# io-board-c-2.net
KiCad netlist of a schematic drawn in EAGLE
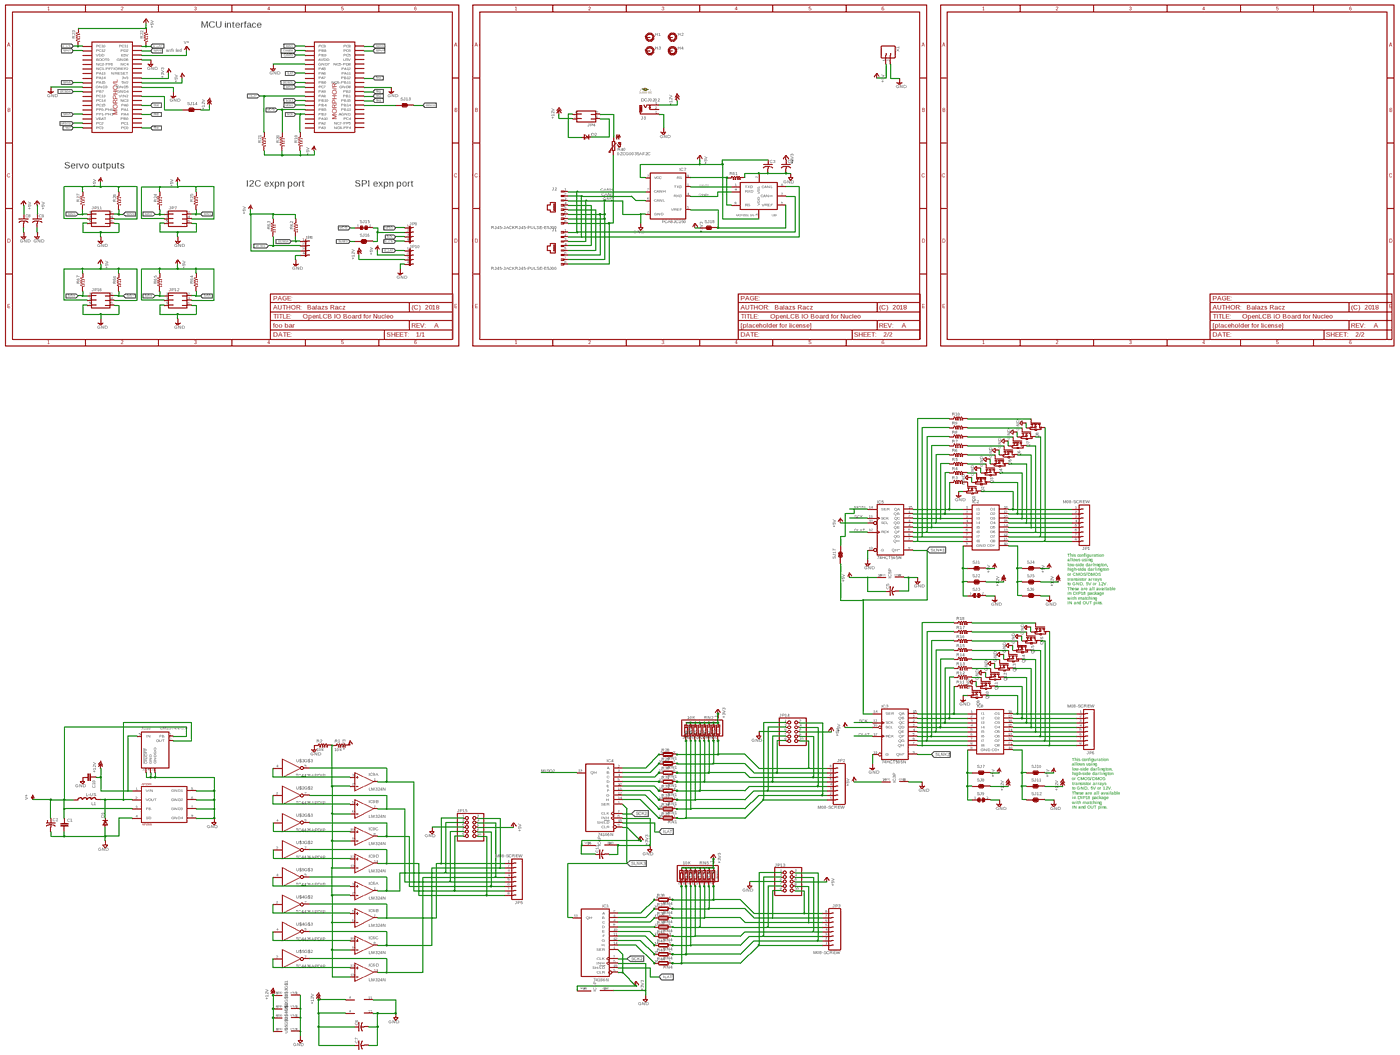
[diagram p0: schematic, sheet 1, overview]
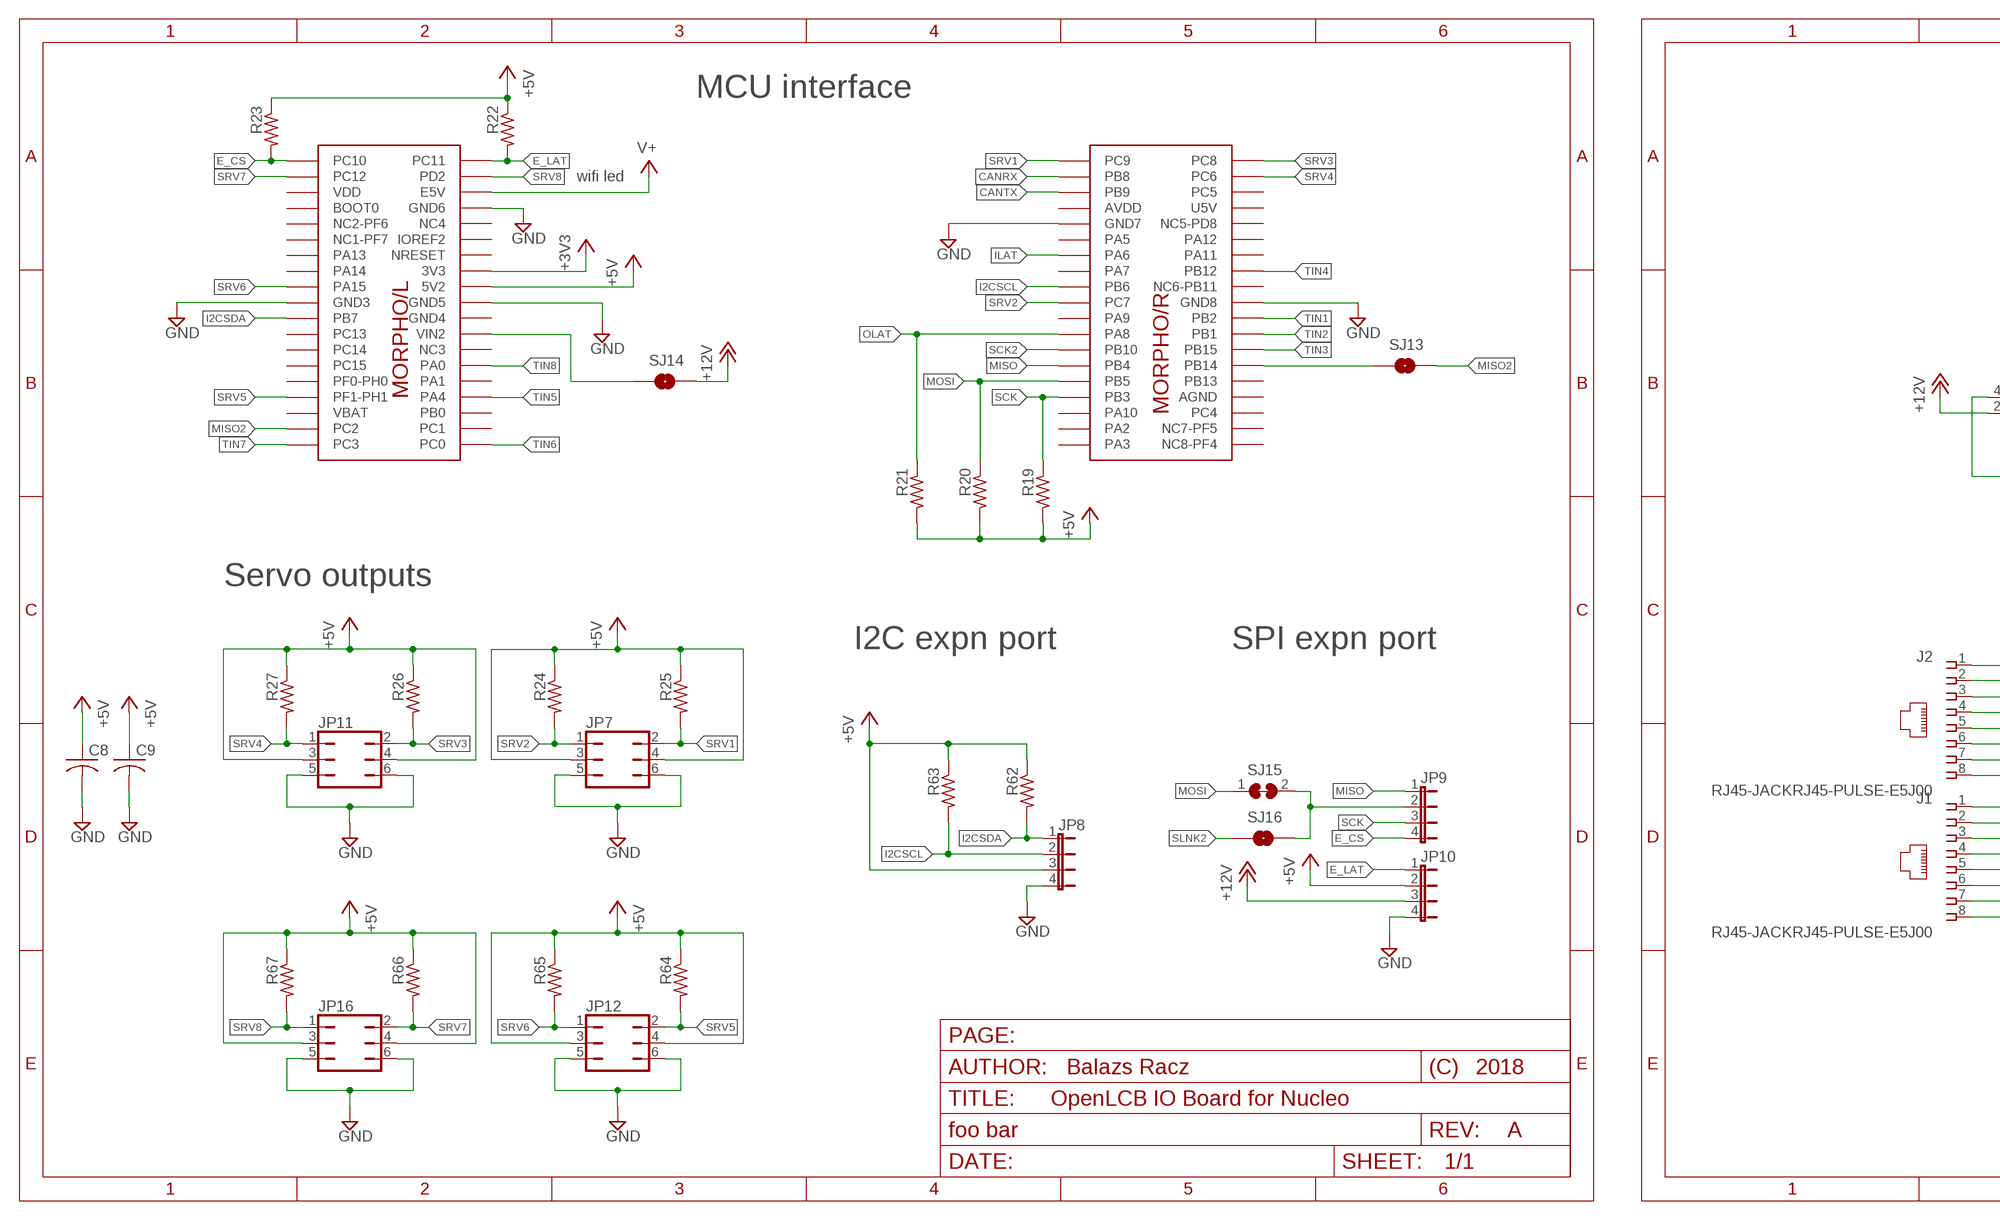
[diagram p1: schematic, sheet 1, part 1 of 4]
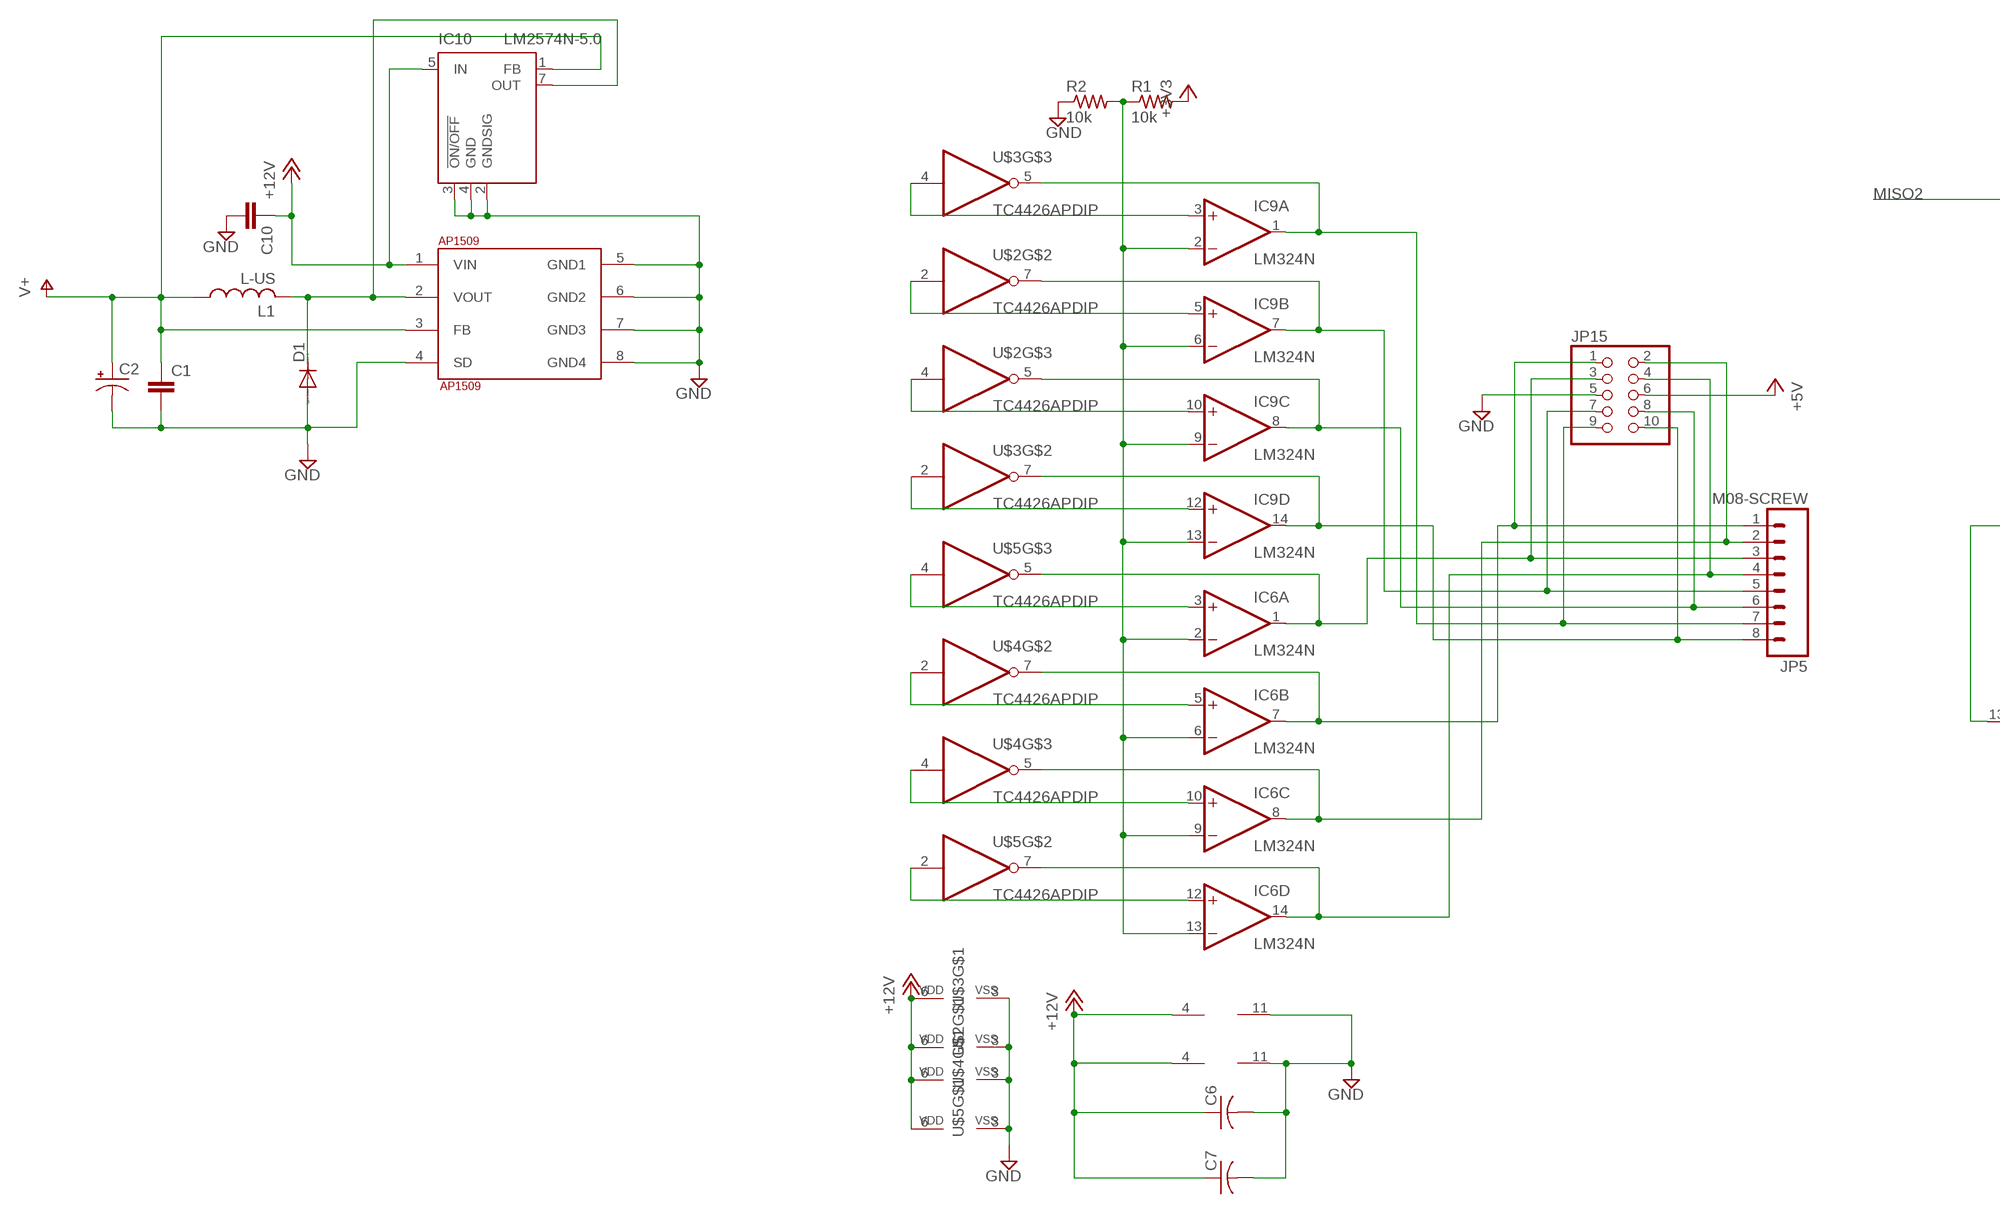
[diagram p2: schematic, sheet 1, part 2 of 4]
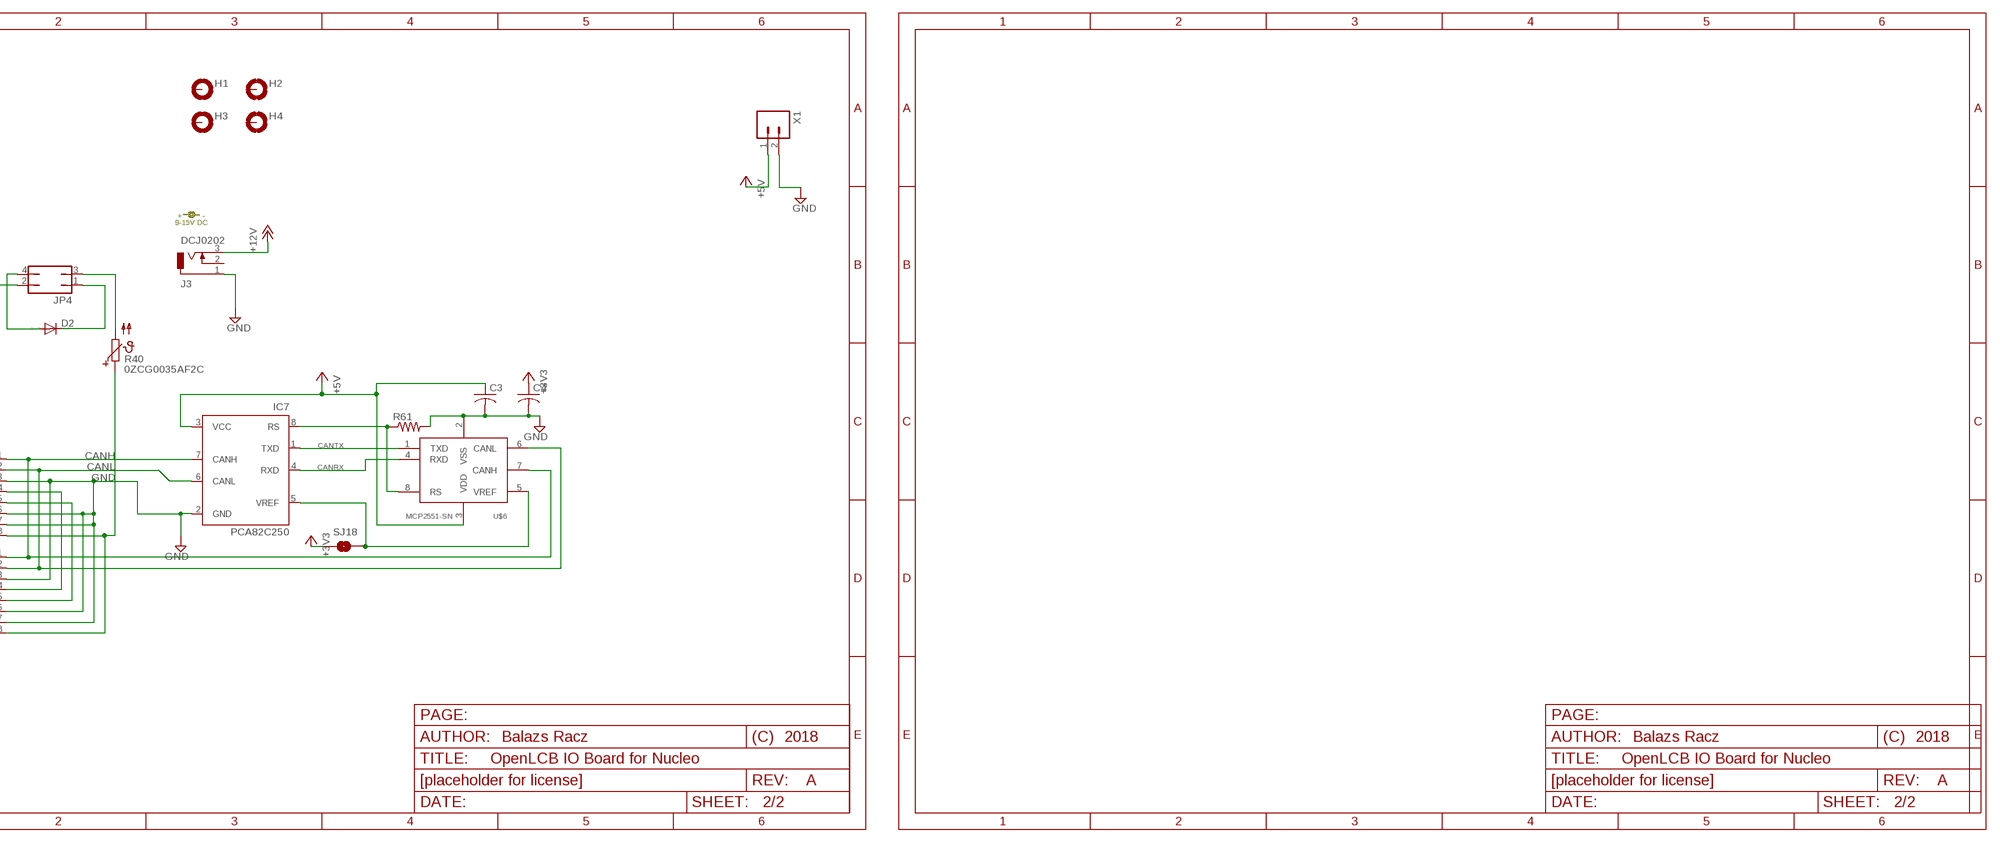
[diagram p3: schematic, sheet 1, part 3 of 4]
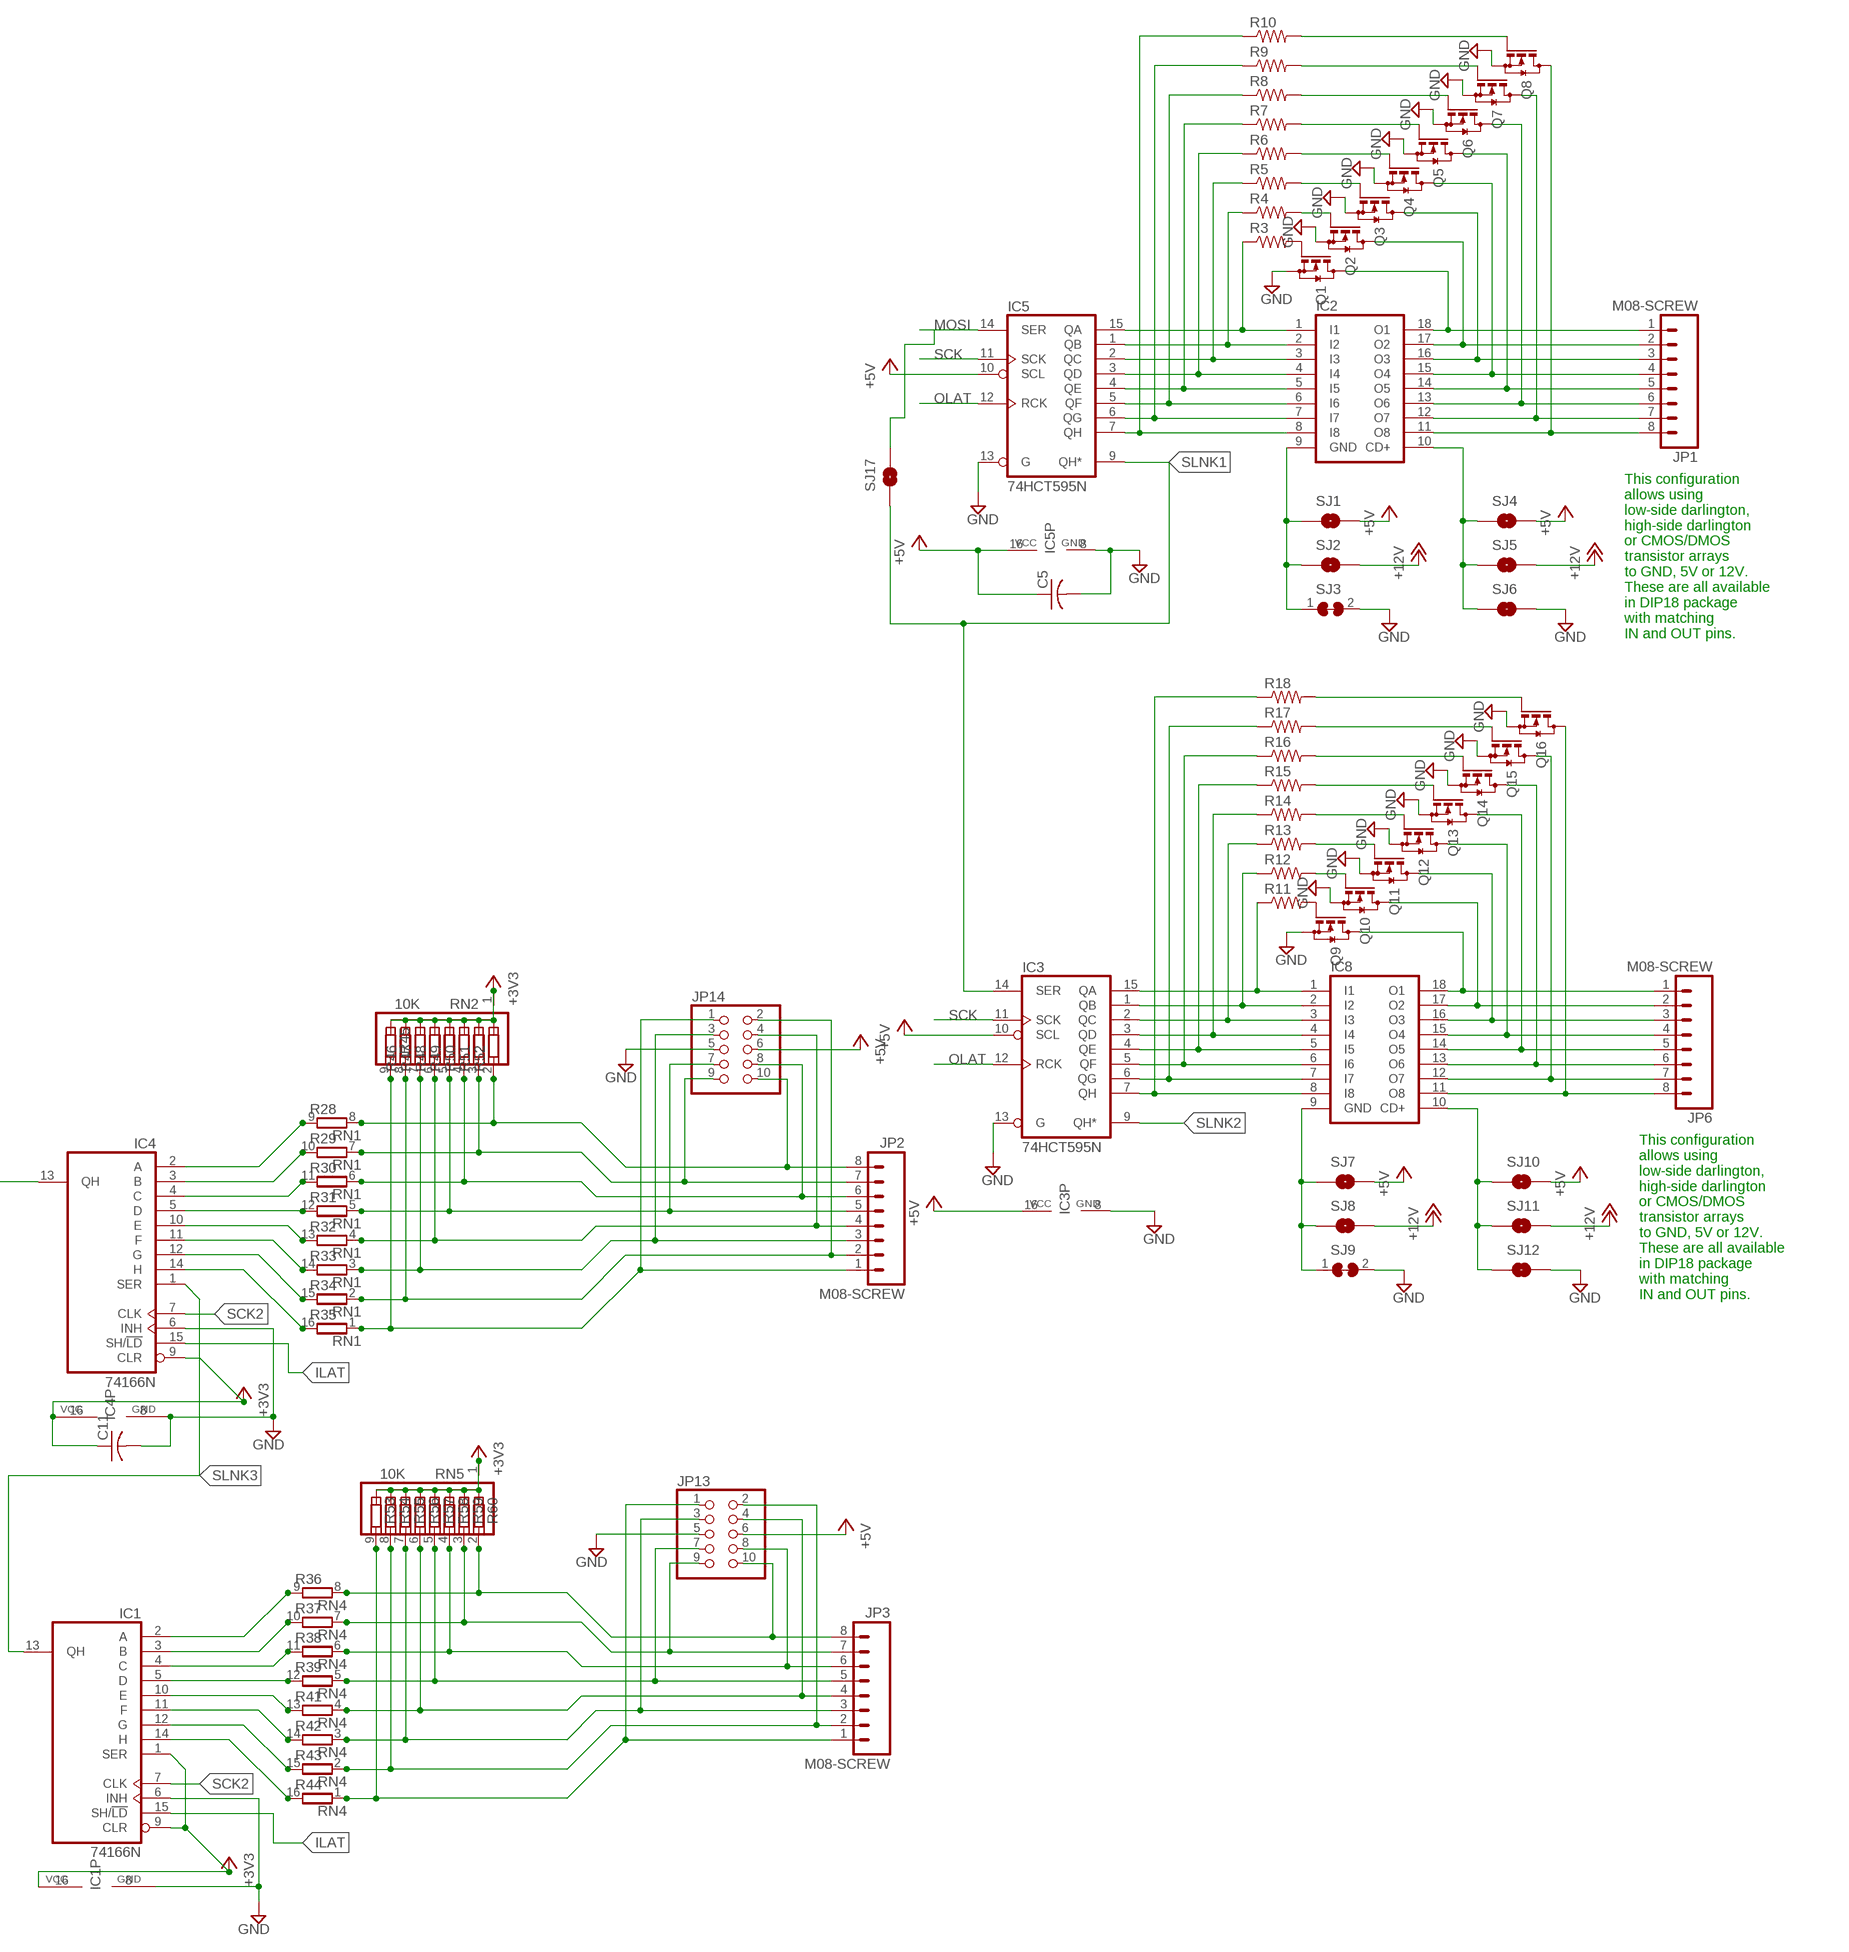
[diagram p4: schematic, sheet 1, part 4 of 4]

(export (version "E")
  (design (tool "Eeschema 10.0.6"))
  (components
    (comp (ref "+12V")
      (value "9-15V DC")
      (footprint "eagle-import:POWER_USAGE")
      (libsource (lib "eagle-import") (part "DOC-POWER_LABEL"))
    )
    (comp (ref "AP1509")
      (value "AP1509")
      (footprint "eagle-import:SO-08")
      (libsource (lib "eagle-import") (part "AP1509"))
    )
    (comp (ref "C1")
      (value "C-EUC1206")
      (footprint "eagle-import:C1206")
      (libsource (lib "eagle-import") (part "C-EUC1206"))
    )
    (comp (ref "C2")
      (value "CPOL-USE2.5-5")
      (footprint "eagle-import:E2,5-5")
      (libsource (lib "eagle-import") (part "CPOL-USE2.5-5"))
    )
    (comp (ref "C3")
      (value "C-USC0805")
      (footprint "eagle-import:C0805")
      (libsource (lib "eagle-import") (part "C-USC0805"))
    )
    (comp (ref "C4")
      (value "C-USC0805")
      (footprint "eagle-import:C0805")
      (libsource (lib "eagle-import") (part "C-USC0805"))
    )
    (comp (ref "C5")
      (value "C-USC0805")
      (footprint "eagle-import:C0805")
      (libsource (lib "eagle-import") (part "C-USC0805"))
    )
    (comp (ref "C6")
      (value "C-USC1206")
      (footprint "eagle-import:C1206")
      (libsource (lib "eagle-import") (part "C-USC1206"))
    )
    (comp (ref "C7")
      (value "C-USC1206")
      (footprint "eagle-import:C1206")
      (libsource (lib "eagle-import") (part "C-USC1206"))
    )
    (comp (ref "C8")
      (value "C-USC1206")
      (footprint "eagle-import:C1206")
      (libsource (lib "eagle-import") (part "C-USC1206"))
    )
    (comp (ref "C9")
      (value "C-USC1206")
      (footprint "eagle-import:C1206")
      (libsource (lib "eagle-import") (part "C-USC1206"))
    )
    (comp (ref "C10")
      (value "C-EUC1206")
      (footprint "eagle-import:C1206")
      (libsource (lib "eagle-import") (part "C-EUC1206"))
    )
    (comp (ref "C11")
      (value "C-USC0805")
      (footprint "eagle-import:C0805")
      (libsource (lib "eagle-import") (part "C-USC0805"))
    )
    (comp (ref "D1")
      (value "DIODE-DO41-7.6")
      (footprint "eagle-import:DO41-7.6")
      (libsource (lib "eagle-import") (part "DIODE-DO41-7.6"))
    )
    (comp (ref "D2")
      (value "DIODE-DO41-7.6")
      (footprint "eagle-import:DO41-7.6")
      (libsource (lib "eagle-import") (part "DIODE-DO41-7.6"))
    )
    (comp (ref "H1")
      (value "MOUNT-PAD-ROUND3.3")
      (footprint "eagle-import:3,3-PAD")
      (libsource (lib "eagle-import") (part "MOUNT-PAD-ROUND3.3"))
    )
    (comp (ref "H2")
      (value "MOUNT-PAD-ROUND3.3")
      (footprint "eagle-import:3,3-PAD")
      (libsource (lib "eagle-import") (part "MOUNT-PAD-ROUND3.3"))
    )
    (comp (ref "H3")
      (value "MOUNT-PAD-ROUND3.3")
      (footprint "eagle-import:3,3-PAD")
      (libsource (lib "eagle-import") (part "MOUNT-PAD-ROUND3.3"))
    )
    (comp (ref "H4")
      (value "MOUNT-PAD-ROUND3.3")
      (footprint "eagle-import:3,3-PAD")
      (libsource (lib "eagle-import") (part "MOUNT-PAD-ROUND3.3"))
    )
    (comp (ref "IC1")
      (value "74166N")
      (footprint "eagle-import:DIL16")
      (libsource (lib "eagle-import") (part "74166N"))
    )
    (comp (ref "IC2")
      (value "ULN2803A")
      (footprint "eagle-import:DIL18-THIN")
      (libsource (lib "eagle-import") (part "ULN2803A"))
    )
    (comp (ref "IC3")
      (value "74HCT595N")
      (footprint "eagle-import:DIL16")
      (libsource (lib "eagle-import") (part "74595NHCT"))
    )
    (comp (ref "IC4")
      (value "74166N")
      (footprint "eagle-import:DIL16")
      (libsource (lib "eagle-import") (part "74166N"))
    )
    (comp (ref "IC5")
      (value "74HCT595N")
      (footprint "eagle-import:DIL16")
      (libsource (lib "eagle-import") (part "74595NHCT"))
    )
    (comp (ref "IC6")
      (value "LM324N")
      (footprint "eagle-import:DIL14")
      (libsource (lib "eagle-import") (part "LM324N"))
    )
    (comp (ref "IC7")
      (value "PCA82C250")
      (footprint "eagle-import:DIL08")
      (libsource (lib "eagle-import") (part "PCA82C250"))
    )
    (comp (ref "IC8")
      (value "ULN2803A")
      (footprint "eagle-import:DIL18-THIN")
      (libsource (lib "eagle-import") (part "ULN2803A"))
    )
    (comp (ref "IC9")
      (value "LM324N")
      (footprint "eagle-import:DIL14")
      (libsource (lib "eagle-import") (part "LM324N"))
    )
    (comp (ref "IC10")
      (value "LM2574N-5.0")
      (footprint "eagle-import:DIL08")
      (libsource (lib "eagle-import") (part "LM2574?-N5.0"))
    )
    (comp (ref "J1")
      (value "RJ45-JACKRJ45-PULSE-E5J00")
      (footprint "eagle-import:RJ45-PULSE-E5J88")
      (libsource (lib "eagle-import") (part "RJ45-JACKRJ45-PULSE-E5J00"))
    )
    (comp (ref "J2")
      (value "RJ45-JACKRJ45-PULSE-E5J00")
      (footprint "eagle-import:RJ45-PULSE-E5J88")
      (libsource (lib "eagle-import") (part "RJ45-JACKRJ45-PULSE-E5J00"))
    )
    (comp (ref "J3")
      (value "DCJ0202")
      (footprint "eagle-import:DCJ0202")
      (libsource (lib "eagle-import") (part "DCJ0202"))
    )
    (comp (ref "JP1")
      (value "M08-SCREW")
      (footprint "eagle-import:1X08_TERMINAL")
      (libsource (lib "eagle-import") (part "M08-SCREW"))
    )
    (comp (ref "JP2")
      (value "M08-SCREW")
      (footprint "eagle-import:1X08_TERMINAL")
      (libsource (lib "eagle-import") (part "M08-SCREW"))
    )
    (comp (ref "JP3")
      (value "M08-SCREW")
      (footprint "eagle-import:1X08_TERMINAL")
      (libsource (lib "eagle-import") (part "M08-SCREW"))
    )
    (comp (ref "JP4")
      (value "JP2Q")
      (footprint "eagle-import:JP2Q")
      (libsource (lib "eagle-import") (part "JP2Q"))
    )
    (comp (ref "JP5")
      (value "M08-SCREW")
      (footprint "eagle-import:1X08_TERMINAL")
      (libsource (lib "eagle-import") (part "M08-SCREW"))
    )
    (comp (ref "JP6")
      (value "M08-SCREW")
      (footprint "eagle-import:1X08_TERMINAL")
      (libsource (lib "eagle-import") (part "M08-SCREW"))
    )
    (comp (ref "JP7")
      (value "JP3Q")
      (footprint "eagle-import:JP3Q")
      (libsource (lib "eagle-import") (part "JP3Q"))
    )
    (comp (ref "JP8")
      (value "JP4-FLAT")
      (footprint "eagle-import:JP4F")
      (libsource (lib "eagle-import") (part "JP4-FLAT"))
    )
    (comp (ref "JP9")
      (value "JP4-FLAT")
      (footprint "eagle-import:JP4F")
      (libsource (lib "eagle-import") (part "JP4-FLAT"))
    )
    (comp (ref "JP10")
      (value "JP4-FLAT")
      (footprint "eagle-import:JP4F")
      (libsource (lib "eagle-import") (part "JP4-FLAT"))
    )
    (comp (ref "JP11")
      (value "JP3Q")
      (footprint "eagle-import:JP3Q")
      (libsource (lib "eagle-import") (part "JP3Q"))
    )
    (comp (ref "JP12")
      (value "JP3Q")
      (footprint "eagle-import:JP3Q")
      (libsource (lib "eagle-import") (part "JP3Q"))
    )
    (comp (ref "JP13")
      (value "PINHD-2X5CN")
      (footprint "eagle-import:CON10M")
      (libsource (lib "eagle-import") (part "PINHD-2X5CN"))
    )
    (comp (ref "JP14")
      (value "PINHD-2X5CN")
      (footprint "eagle-import:CON10M")
      (libsource (lib "eagle-import") (part "PINHD-2X5CN"))
    )
    (comp (ref "JP15")
      (value "PINHD-2X5CN")
      (footprint "eagle-import:CON10M")
      (libsource (lib "eagle-import") (part "PINHD-2X5CN"))
    )
    (comp (ref "JP16")
      (value "JP3Q")
      (footprint "eagle-import:JP3Q")
      (libsource (lib "eagle-import") (part "JP3Q"))
    )
    (comp (ref "L1")
      (value "L-US")
      (footprint "eagle-import:L5-8,5")
      (libsource (lib "eagle-import") (part "L-US"))
    )
    (comp (ref "Q1")
      (value "BSS123")
      (footprint "eagle-import:SOT23")
      (libsource (lib "eagle-import") (part "BSS123"))
    )
    (comp (ref "Q2")
      (value "BSS123")
      (footprint "eagle-import:SOT23")
      (libsource (lib "eagle-import") (part "BSS123"))
    )
    (comp (ref "Q3")
      (value "BSS123")
      (footprint "eagle-import:SOT23")
      (libsource (lib "eagle-import") (part "BSS123"))
    )
    (comp (ref "Q4")
      (value "BSS123")
      (footprint "eagle-import:SOT23")
      (libsource (lib "eagle-import") (part "BSS123"))
    )
    (comp (ref "Q5")
      (value "BSS123")
      (footprint "eagle-import:SOT23")
      (libsource (lib "eagle-import") (part "BSS123"))
    )
    (comp (ref "Q6")
      (value "BSS123")
      (footprint "eagle-import:SOT23")
      (libsource (lib "eagle-import") (part "BSS123"))
    )
    (comp (ref "Q7")
      (value "BSS123")
      (footprint "eagle-import:SOT23")
      (libsource (lib "eagle-import") (part "BSS123"))
    )
    (comp (ref "Q8")
      (value "BSS123")
      (footprint "eagle-import:SOT23")
      (libsource (lib "eagle-import") (part "BSS123"))
    )
    (comp (ref "Q9")
      (value "BSS123")
      (footprint "eagle-import:SOT23")
      (libsource (lib "eagle-import") (part "BSS123"))
    )
    (comp (ref "Q10")
      (value "BSS123")
      (footprint "eagle-import:SOT23")
      (libsource (lib "eagle-import") (part "BSS123"))
    )
    (comp (ref "Q11")
      (value "BSS123")
      (footprint "eagle-import:SOT23")
      (libsource (lib "eagle-import") (part "BSS123"))
    )
    (comp (ref "Q12")
      (value "BSS123")
      (footprint "eagle-import:SOT23")
      (libsource (lib "eagle-import") (part "BSS123"))
    )
    (comp (ref "Q13")
      (value "BSS123")
      (footprint "eagle-import:SOT23")
      (libsource (lib "eagle-import") (part "BSS123"))
    )
    (comp (ref "Q14")
      (value "BSS123")
      (footprint "eagle-import:SOT23")
      (libsource (lib "eagle-import") (part "BSS123"))
    )
    (comp (ref "Q15")
      (value "BSS123")
      (footprint "eagle-import:SOT23")
      (libsource (lib "eagle-import") (part "BSS123"))
    )
    (comp (ref "Q16")
      (value "BSS123")
      (footprint "eagle-import:SOT23")
      (libsource (lib "eagle-import") (part "BSS123"))
    )
    (comp (ref "R1")
      (value "10k")
      (footprint "eagle-import:R0805")
      (libsource (lib "eagle-import") (part "R-US_R0805"))
    )
    (comp (ref "R2")
      (value "10k")
      (footprint "eagle-import:R0805")
      (libsource (lib "eagle-import") (part "R-US_R0805"))
    )
    (comp (ref "R3")
      (value "R-US_R0603")
      (footprint "eagle-import:R0603")
      (libsource (lib "eagle-import") (part "R-US_R0603"))
    )
    (comp (ref "R4")
      (value "R-US_R0603")
      (footprint "eagle-import:R0603")
      (libsource (lib "eagle-import") (part "R-US_R0603"))
    )
    (comp (ref "R5")
      (value "R-US_R0603")
      (footprint "eagle-import:R0603")
      (libsource (lib "eagle-import") (part "R-US_R0603"))
    )
    (comp (ref "R6")
      (value "R-US_R0603")
      (footprint "eagle-import:R0603")
      (libsource (lib "eagle-import") (part "R-US_R0603"))
    )
    (comp (ref "R7")
      (value "R-US_R0603")
      (footprint "eagle-import:R0603")
      (libsource (lib "eagle-import") (part "R-US_R0603"))
    )
    (comp (ref "R8")
      (value "R-US_R0603")
      (footprint "eagle-import:R0603")
      (libsource (lib "eagle-import") (part "R-US_R0603"))
    )
    (comp (ref "R9")
      (value "R-US_R0603")
      (footprint "eagle-import:R0603")
      (libsource (lib "eagle-import") (part "R-US_R0603"))
    )
    (comp (ref "R10")
      (value "R-US_R0603")
      (footprint "eagle-import:R0603")
      (libsource (lib "eagle-import") (part "R-US_R0603"))
    )
    (comp (ref "R11")
      (value "R-US_R0603")
      (footprint "eagle-import:R0603")
      (libsource (lib "eagle-import") (part "R-US_R0603"))
    )
    (comp (ref "R12")
      (value "R-US_R0603")
      (footprint "eagle-import:R0603")
      (libsource (lib "eagle-import") (part "R-US_R0603"))
    )
    (comp (ref "R13")
      (value "R-US_R0603")
      (footprint "eagle-import:R0603")
      (libsource (lib "eagle-import") (part "R-US_R0603"))
    )
    (comp (ref "R14")
      (value "R-US_R0603")
      (footprint "eagle-import:R0603")
      (libsource (lib "eagle-import") (part "R-US_R0603"))
    )
    (comp (ref "R15")
      (value "R-US_R0603")
      (footprint "eagle-import:R0603")
      (libsource (lib "eagle-import") (part "R-US_R0603"))
    )
    (comp (ref "R16")
      (value "R-US_R0603")
      (footprint "eagle-import:R0603")
      (libsource (lib "eagle-import") (part "R-US_R0603"))
    )
    (comp (ref "R17")
      (value "R-US_R0603")
      (footprint "eagle-import:R0603")
      (libsource (lib "eagle-import") (part "R-US_R0603"))
    )
    (comp (ref "R18")
      (value "R-US_R0603")
      (footprint "eagle-import:R0603")
      (libsource (lib "eagle-import") (part "R-US_R0603"))
    )
    (comp (ref "R19")
      (value "R-US_R0805")
      (footprint "eagle-import:R0805")
      (libsource (lib "eagle-import") (part "rcl_334_R-US_R0805"))
    )
    (comp (ref "R20")
      (value "R-US_R0805")
      (footprint "eagle-import:R0805")
      (libsource (lib "eagle-import") (part "rcl_334_R-US_R0805"))
    )
    (comp (ref "R21")
      (value "R-US_R0805")
      (footprint "eagle-import:R0805")
      (libsource (lib "eagle-import") (part "rcl_334_R-US_R0805"))
    )
    (comp (ref "R22")
      (value "R-US_R0805")
      (footprint "eagle-import:R0805")
      (libsource (lib "eagle-import") (part "rcl_334_R-US_R0805"))
    )
    (comp (ref "R23")
      (value "R-US_R0805")
      (footprint "eagle-import:R0805")
      (libsource (lib "eagle-import") (part "rcl_334_R-US_R0805"))
    )
    (comp (ref "R24")
      (value "R-US_R0805")
      (footprint "eagle-import:R0805")
      (libsource (lib "eagle-import") (part "rcl_334_R-US_R0805"))
    )
    (comp (ref "R25")
      (value "R-US_R0805")
      (footprint "eagle-import:R0805")
      (libsource (lib "eagle-import") (part "rcl_334_R-US_R0805"))
    )
    (comp (ref "R26")
      (value "R-US_R0805")
      (footprint "eagle-import:R0805")
      (libsource (lib "eagle-import") (part "rcl_334_R-US_R0805"))
    )
    (comp (ref "R27")
      (value "R-US_R0805")
      (footprint "eagle-import:R0805")
      (libsource (lib "eagle-import") (part "rcl_334_R-US_R0805"))
    )
    (comp (ref "R28")
      (value "R-EU_R0603")
      (footprint "eagle-import:R0603")
      (libsource (lib "eagle-import") (part "R-EU_R0603"))
    )
    (comp (ref "R29")
      (value "R-EU_R0603")
      (footprint "eagle-import:R0603")
      (libsource (lib "eagle-import") (part "R-EU_R0603"))
    )
    (comp (ref "R30")
      (value "R-EU_R0603")
      (footprint "eagle-import:R0603")
      (libsource (lib "eagle-import") (part "R-EU_R0603"))
    )
    (comp (ref "R31")
      (value "R-EU_R0603")
      (footprint "eagle-import:R0603")
      (libsource (lib "eagle-import") (part "R-EU_R0603"))
    )
    (comp (ref "R32")
      (value "R-EU_R0603")
      (footprint "eagle-import:R0603")
      (libsource (lib "eagle-import") (part "R-EU_R0603"))
    )
    (comp (ref "R33")
      (value "R-EU_R0603")
      (footprint "eagle-import:R0603")
      (libsource (lib "eagle-import") (part "R-EU_R0603"))
    )
    (comp (ref "R34")
      (value "R-EU_R0603")
      (footprint "eagle-import:R0603")
      (libsource (lib "eagle-import") (part "R-EU_R0603"))
    )
    (comp (ref "R35")
      (value "R-EU_R0603")
      (footprint "eagle-import:R0603")
      (libsource (lib "eagle-import") (part "R-EU_R0603"))
    )
    (comp (ref "R36")
      (value "R-EU_R0603")
      (footprint "eagle-import:R0603")
      (libsource (lib "eagle-import") (part "R-EU_R0603"))
    )
    (comp (ref "R37")
      (value "R-EU_R0603")
      (footprint "eagle-import:R0603")
      (libsource (lib "eagle-import") (part "R-EU_R0603"))
    )
    (comp (ref "R38")
      (value "R-EU_R0603")
      (footprint "eagle-import:R0603")
      (libsource (lib "eagle-import") (part "R-EU_R0603"))
    )
    (comp (ref "R39")
      (value "R-EU_R0603")
      (footprint "eagle-import:R0603")
      (libsource (lib "eagle-import") (part "R-EU_R0603"))
    )
    (comp (ref "R40")
      (value "0ZCG0035AF2C")
      (footprint "eagle-import:PTC1812")
      (libsource (lib "eagle-import") (part "PTC_1812"))
    )
    (comp (ref "R41")
      (value "R-EU_R0603")
      (footprint "eagle-import:R0603")
      (libsource (lib "eagle-import") (part "R-EU_R0603"))
    )
    (comp (ref "R42")
      (value "R-EU_R0603")
      (footprint "eagle-import:R0603")
      (libsource (lib "eagle-import") (part "R-EU_R0603"))
    )
    (comp (ref "R43")
      (value "R-EU_R0603")
      (footprint "eagle-import:R0603")
      (libsource (lib "eagle-import") (part "R-EU_R0603"))
    )
    (comp (ref "R44")
      (value "R-EU_R0603")
      (footprint "eagle-import:R0603")
      (libsource (lib "eagle-import") (part "R-EU_R0603"))
    )
    (comp (ref "R45")
      (value "R-EU_R0603")
      (footprint "eagle-import:R0603")
      (libsource (lib "eagle-import") (part "R-EU_R0603"))
    )
    (comp (ref "R46")
      (value "R-EU_R0603")
      (footprint "eagle-import:R0603")
      (libsource (lib "eagle-import") (part "R-EU_R0603"))
    )
    (comp (ref "R47")
      (value "R-EU_R0603")
      (footprint "eagle-import:R0603")
      (libsource (lib "eagle-import") (part "R-EU_R0603"))
    )
    (comp (ref "R48")
      (value "R-EU_R0603")
      (footprint "eagle-import:R0603")
      (libsource (lib "eagle-import") (part "R-EU_R0603"))
    )
    (comp (ref "R49")
      (value "R-EU_R0603")
      (footprint "eagle-import:R0603")
      (libsource (lib "eagle-import") (part "R-EU_R0603"))
    )
    (comp (ref "R50")
      (value "R-EU_R0603")
      (footprint "eagle-import:R0603")
      (libsource (lib "eagle-import") (part "R-EU_R0603"))
    )
    (comp (ref "R51")
      (value "R-EU_R0603")
      (footprint "eagle-import:R0603")
      (libsource (lib "eagle-import") (part "R-EU_R0603"))
    )
    (comp (ref "R52")
      (value "R-EU_R0603")
      (footprint "eagle-import:R0603")
      (libsource (lib "eagle-import") (part "R-EU_R0603"))
    )
    (comp (ref "R53")
      (value "R-EU_R0603")
      (footprint "eagle-import:R0603")
      (libsource (lib "eagle-import") (part "R-EU_R0603"))
    )
    (comp (ref "R54")
      (value "R-EU_R0603")
      (footprint "eagle-import:R0603")
      (libsource (lib "eagle-import") (part "R-EU_R0603"))
    )
    (comp (ref "R55")
      (value "R-EU_R0603")
      (footprint "eagle-import:R0603")
      (libsource (lib "eagle-import") (part "R-EU_R0603"))
    )
    (comp (ref "R56")
      (value "R-EU_R0603")
      (footprint "eagle-import:R0603")
      (libsource (lib "eagle-import") (part "R-EU_R0603"))
    )
    (comp (ref "R57")
      (value "R-EU_R0603")
      (footprint "eagle-import:R0603")
      (libsource (lib "eagle-import") (part "R-EU_R0603"))
    )
    (comp (ref "R58")
      (value "R-EU_R0603")
      (footprint "eagle-import:R0603")
      (libsource (lib "eagle-import") (part "R-EU_R0603"))
    )
    (comp (ref "R59")
      (value "R-EU_R0603")
      (footprint "eagle-import:R0603")
      (libsource (lib "eagle-import") (part "R-EU_R0603"))
    )
    (comp (ref "R60")
      (value "R-EU_R0603")
      (footprint "eagle-import:R0603")
      (libsource (lib "eagle-import") (part "R-EU_R0603"))
    )
    (comp (ref "R61")
      (value "R-US_R0805")
      (footprint "eagle-import:R0805")
      (libsource (lib "eagle-import") (part "rcl_334_R-US_R0805"))
    )
    (comp (ref "R62")
      (value "R-US_R0805")
      (footprint "eagle-import:R0805")
      (libsource (lib "eagle-import") (part "rcl_334_R-US_R0805"))
    )
    (comp (ref "R63")
      (value "R-US_R0805")
      (footprint "eagle-import:R0805")
      (libsource (lib "eagle-import") (part "rcl_334_R-US_R0805"))
    )
    (comp (ref "R64")
      (value "R-US_R0805")
      (footprint "eagle-import:R0805")
      (libsource (lib "eagle-import") (part "rcl_334_R-US_R0805"))
    )
    (comp (ref "R65")
      (value "R-US_R0805")
      (footprint "eagle-import:R0805")
      (libsource (lib "eagle-import") (part "rcl_334_R-US_R0805"))
    )
    (comp (ref "R66")
      (value "R-US_R0805")
      (footprint "eagle-import:R0805")
      (libsource (lib "eagle-import") (part "rcl_334_R-US_R0805"))
    )
    (comp (ref "R67")
      (value "R-US_R0805")
      (footprint "eagle-import:R0805")
      (libsource (lib "eagle-import") (part "rcl_334_R-US_R0805"))
    )
    (comp (ref "RN1")
      (value "8R-P")
      (footprint "eagle-import:DIL16")
      (libsource (lib "eagle-import") (part "8R-P"))
    )
    (comp (ref "RN2")
      (value "10K")
      (footprint "eagle-import:SIL9")
      (libsource (lib "eagle-import") (part "G08R"))
    )
    (comp (ref "RN4")
      (value "8R-P")
      (footprint "eagle-import:DIL16")
      (libsource (lib "eagle-import") (part "8R-P"))
    )
    (comp (ref "RN5")
      (value "10K")
      (footprint "eagle-import:SIL9")
      (libsource (lib "eagle-import") (part "G08R"))
    )
    (comp (ref "SJ1")
      (value "SJRND2")
      (footprint "eagle-import:SJ_RND2")
      (libsource (lib "eagle-import") (part "SJRND2"))
    )
    (comp (ref "SJ2")
      (value "SJRND2")
      (footprint "eagle-import:SJ_RND2")
      (libsource (lib "eagle-import") (part "SJRND2"))
    )
    (comp (ref "SJ3")
      (value "SJ-C")
      (footprint "eagle-import:SJW-C")
      (libsource (lib "eagle-import") (part "SJ-C"))
    )
    (comp (ref "SJ4")
      (value "SJRND2")
      (footprint "eagle-import:SJ_RND2")
      (libsource (lib "eagle-import") (part "SJRND2"))
    )
    (comp (ref "SJ5")
      (value "SJRND2")
      (footprint "eagle-import:SJ_RND2")
      (libsource (lib "eagle-import") (part "SJRND2"))
    )
    (comp (ref "SJ6")
      (value "SJRND2")
      (footprint "eagle-import:SJ_RND2")
      (libsource (lib "eagle-import") (part "SJRND2"))
    )
    (comp (ref "SJ7")
      (value "SJRND2")
      (footprint "eagle-import:SJ_RND2")
      (libsource (lib "eagle-import") (part "SJRND2"))
    )
    (comp (ref "SJ8")
      (value "SJRND2")
      (footprint "eagle-import:SJ_RND2")
      (libsource (lib "eagle-import") (part "SJRND2"))
    )
    (comp (ref "SJ9")
      (value "SJ-C")
      (footprint "eagle-import:SJW-C")
      (libsource (lib "eagle-import") (part "SJ-C"))
    )
    (comp (ref "SJ10")
      (value "SJRND2")
      (footprint "eagle-import:SJ_RND2")
      (libsource (lib "eagle-import") (part "SJRND2"))
    )
    (comp (ref "SJ11")
      (value "SJRND2")
      (footprint "eagle-import:SJ_RND2")
      (libsource (lib "eagle-import") (part "SJRND2"))
    )
    (comp (ref "SJ12")
      (value "SJRND2")
      (footprint "eagle-import:SJ_RND2")
      (libsource (lib "eagle-import") (part "SJRND2"))
    )
    (comp (ref "SJ13")
      (value "SJRND2")
      (footprint "eagle-import:SJ_RND2")
      (libsource (lib "eagle-import") (part "SJRND2"))
    )
    (comp (ref "SJ14")
      (value "SJRND2")
      (footprint "eagle-import:SJ_RND2")
      (libsource (lib "eagle-import") (part "SJRND2"))
    )
    (comp (ref "SJ15")
      (value "SJ-C")
      (footprint "eagle-import:SJW-C")
      (libsource (lib "eagle-import") (part "SJ-C"))
    )
    (comp (ref "SJ16")
      (value "SJRND2")
      (footprint "eagle-import:SJ_RND2")
      (libsource (lib "eagle-import") (part "SJRND2"))
    )
    (comp (ref "SJ17")
      (value "SJRND2")
      (footprint "eagle-import:SJ_RND2")
      (libsource (lib "eagle-import") (part "SJRND2"))
    )
    (comp (ref "SJ18")
      (value "SJRND2")
      (footprint "eagle-import:SJ_RND2")
      (libsource (lib "eagle-import") (part "SJRND2"))
    )
    (comp (ref "U$1")
      (value "NUCLEO_64_GENERIC")
      (footprint "eagle-import:NUCLEO_BRD_BASE64")
      (libsource (lib "eagle-import") (part "NUCLEO_64_GENERIC"))
    )
    (comp (ref "U$2")
      (value "TC4426APDIP")
      (footprint "eagle-import:DIL08-LONG")
      (libsource (lib "eagle-import") (part "TC4426APDIP"))
    )
    (comp (ref "U$3")
      (value "TC4426APDIP")
      (footprint "eagle-import:DIL08-LONG")
      (libsource (lib "eagle-import") (part "TC4426APDIP"))
    )
    (comp (ref "U$4")
      (value "TC4426APDIP")
      (footprint "eagle-import:DIL08-LONG")
      (libsource (lib "eagle-import") (part "TC4426APDIP"))
    )
    (comp (ref "U$5")
      (value "TC4426APDIP")
      (footprint "eagle-import:DIL08-LONG")
      (libsource (lib "eagle-import") (part "TC4426APDIP"))
    )
    (comp (ref "U$6")
      (value "MCP2551-SN")
      (footprint "eagle-import:SO-08")
      (libsource (lib "eagle-import") (part "MCP2551-SN"))
    )
    (comp (ref "X1")
      (value "CONNECTOR-M023.5MM-LOCK")
      (footprint "eagle-import:SCREWTERMINAL-3.5MM-2_LOCK")
      (libsource (lib "eagle-import") (part "CONNECTOR-M023.5MM-LOCK"))
    )
  )
  (nets
    (net (code "1") (name "+3V3") (class "Default")
      (node (ref "C11") (pin "1") (pinfunction "1_1") (pintype "passive"))
      (node (ref "C4") (pin "1") (pinfunction "1_1") (pintype "passive"))
      (node (ref "IC1") (pin "1") (pinfunction "SER_1") (pintype "input"))
      (node (ref "IC1") (pin "16") (pinfunction "VCC_16") (pintype "power_in"))
      (node (ref "IC1") (pin "9") (pinfunction "CLR_9") (pintype "input"))
      (node (ref "IC4") (pin "16") (pinfunction "VCC_16") (pintype "power_in"))
      (node (ref "IC4") (pin "9") (pinfunction "CLR_9") (pintype "input"))
      (node (ref "R1") (pin "2") (pinfunction "2_2") (pintype "passive"))
      (node (ref "R45") (pin "1") (pinfunction "1_1") (pintype "passive"))
      (node (ref "R46") (pin "2") (pinfunction "2_2") (pintype "passive"))
      (node (ref "R47") (pin "2") (pinfunction "2_2") (pintype "passive"))
      (node (ref "R48") (pin "2") (pinfunction "2_2") (pintype "passive"))
      (node (ref "R49") (pin "2") (pinfunction "2_2") (pintype "passive"))
      (node (ref "R50") (pin "2") (pinfunction "2_2") (pintype "passive"))
      (node (ref "R51") (pin "2") (pinfunction "2_2") (pintype "passive"))
      (node (ref "R52") (pin "2") (pinfunction "2_2") (pintype "passive"))
      (node (ref "R53") (pin "1") (pinfunction "1_1") (pintype "passive"))
      (node (ref "R54") (pin "1") (pinfunction "1_1") (pintype "passive"))
      (node (ref "R55") (pin "1") (pinfunction "1_1") (pintype "passive"))
      (node (ref "R56") (pin "1") (pinfunction "1_1") (pintype "passive"))
      (node (ref "R57") (pin "1") (pinfunction "1_1") (pintype "passive"))
      (node (ref "R58") (pin "1") (pinfunction "1_1") (pintype "passive"))
      (node (ref "R59") (pin "1") (pinfunction "1_1") (pintype "passive"))
      (node (ref "R60") (pin "1") (pinfunction "1_1") (pintype "passive"))
      (node (ref "RN2") (pin "1") (pinfunction "1_1") (pintype "passive"))
      (node (ref "RN5") (pin "1") (pinfunction "1_1") (pintype "passive"))
      (node (ref "SJ18") (pin "P$1") (pinfunction "1_P$1") (pintype "passive"))
      (node (ref "U$1") (pin "3V3") (pinfunction "3V3_3V3") (pintype "power_in"))
    )
    (net (code "2") (name "+5V") (class "Default")
      (node (ref "C3") (pin "1") (pinfunction "1_1") (pintype "passive"))
      (node (ref "C5") (pin "1") (pinfunction "1_1") (pintype "passive"))
      (node (ref "C8") (pin "1") (pinfunction "1_1") (pintype "passive"))
      (node (ref "C9") (pin "1") (pinfunction "1_1") (pintype "passive"))
      (node (ref "IC3") (pin "10") (pinfunction "SCL_10") (pintype "input"))
      (node (ref "IC3") (pin "16") (pinfunction "VCC_16") (pintype "power_in"))
      (node (ref "IC5") (pin "10") (pinfunction "SCL_10") (pintype "input"))
      (node (ref "IC5") (pin "16") (pinfunction "VCC_16") (pintype "power_in"))
      (node (ref "IC7") (pin "3") (pinfunction "VCC_3") (pintype "power_in"))
      (node (ref "JP10") (pin "2") (pinfunction "2_2") (pintype "passive"))
      (node (ref "JP11") (pin "3") (pinfunction "3_3") (pintype "passive"))
      (node (ref "JP11") (pin "4") (pinfunction "4_4") (pintype "passive"))
      (node (ref "JP12") (pin "3") (pinfunction "3_3") (pintype "passive"))
      (node (ref "JP12") (pin "4") (pinfunction "4_4") (pintype "passive"))
      (node (ref "JP13") (pin "6") (pinfunction "6_6") (pintype "passive"))
      (node (ref "JP14") (pin "6") (pinfunction "6_6") (pintype "passive"))
      (node (ref "JP15") (pin "6") (pinfunction "6_6") (pintype "passive"))
      (node (ref "JP16") (pin "3") (pinfunction "3_3") (pintype "passive"))
      (node (ref "JP16") (pin "4") (pinfunction "4_4") (pintype "passive"))
      (node (ref "JP7") (pin "3") (pinfunction "3_3") (pintype "passive"))
      (node (ref "JP7") (pin "4") (pinfunction "4_4") (pintype "passive"))
      (node (ref "JP8") (pin "3") (pinfunction "3_3") (pintype "passive"))
      (node (ref "R19") (pin "2") (pinfunction "2_2") (pintype "passive"))
      (node (ref "R20") (pin "2") (pinfunction "2_2") (pintype "passive"))
      (node (ref "R21") (pin "2") (pinfunction "2_2") (pintype "passive"))
      (node (ref "R22") (pin "1") (pinfunction "1_1") (pintype "passive"))
      (node (ref "R23") (pin "1") (pinfunction "1_1") (pintype "passive"))
      (node (ref "R24") (pin "1") (pinfunction "1_1") (pintype "passive"))
      (node (ref "R25") (pin "1") (pinfunction "1_1") (pintype "passive"))
      (node (ref "R26") (pin "1") (pinfunction "1_1") (pintype "passive"))
      (node (ref "R27") (pin "1") (pinfunction "1_1") (pintype "passive"))
      (node (ref "R62") (pin "1") (pinfunction "1_1") (pintype "passive"))
      (node (ref "R63") (pin "1") (pinfunction "1_1") (pintype "passive"))
      (node (ref "R64") (pin "1") (pinfunction "1_1") (pintype "passive"))
      (node (ref "R65") (pin "1") (pinfunction "1_1") (pintype "passive"))
      (node (ref "R66") (pin "1") (pinfunction "1_1") (pintype "passive"))
      (node (ref "R67") (pin "1") (pinfunction "1_1") (pintype "passive"))
      (node (ref "SJ1") (pin "P$2") (pinfunction "2_P$2") (pintype "passive"))
      (node (ref "SJ10") (pin "P$2") (pinfunction "2_P$2") (pintype "passive"))
      (node (ref "SJ4") (pin "P$2") (pinfunction "2_P$2") (pintype "passive"))
      (node (ref "SJ7") (pin "P$2") (pinfunction "2_P$2") (pintype "passive"))
      (node (ref "U$1") (pin "5V2") (pinfunction "5V2_5V2") (pintype "power_in"))
      (node (ref "U$6") (pin "3") (pinfunction "VDD_3") (pintype "power_in"))
      (node (ref "X1") (pin "1") (pinfunction "1_1") (pintype "passive"))
    )
    (net (code "3") (name "+12V") (class "Default")
      (node (ref "AP1509") (pin "1") (pinfunction "VIN_1") (pintype "bidirectional"))
      (node (ref "C10") (pin "1") (pinfunction "1_1") (pintype "passive"))
      (node (ref "C6") (pin "1") (pinfunction "1_1") (pintype "passive"))
      (node (ref "C7") (pin "1") (pinfunction "1_1") (pintype "passive"))
      (node (ref "IC10") (pin "5") (pinfunction "IN_5") (pintype "input"))
      (node (ref "IC6") (pin "4") (pinfunction "V+_4") (pintype "power_in"))
      (node (ref "IC9") (pin "4") (pinfunction "V+_4") (pintype "power_in"))
      (node (ref "J3") (pin "3") (pinfunction "3_3") (pintype "passive"))
      (node (ref "JP10") (pin "3") (pinfunction "3_3") (pintype "passive"))
      (node (ref "JP4") (pin "2") (pinfunction "2_2") (pintype "passive"))
      (node (ref "SJ11") (pin "P$2") (pinfunction "2_P$2") (pintype "passive"))
      (node (ref "SJ14") (pin "P$2") (pinfunction "2_P$2") (pintype "passive"))
      (node (ref "SJ2") (pin "P$2") (pinfunction "2_P$2") (pintype "passive"))
      (node (ref "SJ5") (pin "P$2") (pinfunction "2_P$2") (pintype "passive"))
      (node (ref "SJ8") (pin "P$2") (pinfunction "2_P$2") (pintype "passive"))
      (node (ref "U$2") (pin "6") (pinfunction "VDD_6") (pintype "power_in"))
      (node (ref "U$3") (pin "6") (pinfunction "VDD_6") (pintype "power_in"))
      (node (ref "U$4") (pin "6") (pinfunction "VDD_6") (pintype "power_in"))
      (node (ref "U$5") (pin "6") (pinfunction "VDD_6") (pintype "power_in"))
    )
    (net (code "4") (name "/AGND") (class "Default")
      (node (ref "U$1") (pin "AGND") (pinfunction "AGND_AGND") (pintype "power_in"))
    )
    (net (code "5") (name "/AVDD") (class "Default")
      (node (ref "U$1") (pin "AVDD") (pinfunction "AVDD_AVDD") (pintype "power_in"))
    )
    (net (code "6") (name "/CANH") (class "Default")
      (node (ref "IC7") (pin "7") (pinfunction "CANH_7") (pintype "bidirectional"))
      (node (ref "J1") (pin "1") (pinfunction "1_1") (pintype "passive"))
      (node (ref "J2") (pin "1") (pinfunction "1_1") (pintype "passive"))
      (node (ref "U$6") (pin "7") (pinfunction "CANH_7") (pintype "bidirectional"))
    )
    (net (code "7") (name "/CANL") (class "Default")
      (node (ref "IC7") (pin "6") (pinfunction "CANL_6") (pintype "bidirectional"))
      (node (ref "J1") (pin "2") (pinfunction "2_2") (pintype "passive"))
      (node (ref "J2") (pin "2") (pinfunction "2_2") (pintype "passive"))
      (node (ref "U$6") (pin "6") (pinfunction "CANL_6") (pintype "bidirectional"))
    )
    (net (code "8") (name "/GND4") (class "Default")
      (node (ref "U$1") (pin "GND4") (pinfunction "GND4_GND4") (pintype "power_in"))
    )
    (net (code "9") (name "/U5V") (class "Default")
      (node (ref "U$1") (pin "U5V") (pinfunction "U5V_U5V") (pintype "power_in"))
    )
    (net (code "10") (name "/VBAT") (class "Default")
      (node (ref "U$1") (pin "VBAT") (pinfunction "VBAT_VBAT") (pintype "power_in"))
    )
    (net (code "11") (name "/VDD") (class "Default")
      (node (ref "U$1") (pin "VDD") (pinfunction "VDD_VDD") (pintype "power_in"))
    )
    (net (code "12") (name "CANRX") (class "Default")
      (node (ref "IC7") (pin "4") (pinfunction "RXD_4") (pintype "output"))
      (node (ref "U$1") (pin "PB8") (pinfunction "PB8_PB8") (pintype "bidirectional"))
      (node (ref "U$6") (pin "4") (pinfunction "RXD_4") (pintype "bidirectional"))
    )
    (net (code "13") (name "CANTX") (class "Default")
      (node (ref "IC7") (pin "1") (pinfunction "TXD_1") (pintype "input"))
      (node (ref "U$1") (pin "PB9") (pinfunction "PB9_PB9") (pintype "bidirectional"))
      (node (ref "U$6") (pin "1") (pinfunction "TXD_1") (pintype "bidirectional"))
    )
    (net (code "14") (name "E_CS") (class "Default")
      (node (ref "JP9") (pin "4") (pinfunction "4_4") (pintype "passive"))
      (node (ref "R23") (pin "2") (pinfunction "2_2") (pintype "passive"))
      (node (ref "U$1") (pin "PC10") (pinfunction "PC10_PC10") (pintype "bidirectional"))
    )
    (net (code "15") (name "E_LAT") (class "Default")
      (node (ref "JP10") (pin "1") (pinfunction "1_1") (pintype "passive"))
      (node (ref "R22") (pin "2") (pinfunction "2_2") (pintype "passive"))
      (node (ref "U$1") (pin "PC11") (pinfunction "PC11_PC11") (pintype "bidirectional"))
    )
    (net (code "16") (name "GND") (class "Default")
      (node (ref "AP1509") (pin "4") (pinfunction "SD_4") (pintype "bidirectional"))
      (node (ref "AP1509") (pin "5") (pinfunction "GND1_5") (pintype "power_in"))
      (node (ref "AP1509") (pin "6") (pinfunction "GND2_6") (pintype "power_in"))
      (node (ref "AP1509") (pin "7") (pinfunction "GND3_7") (pintype "power_in"))
      (node (ref "AP1509") (pin "8") (pinfunction "GND4_8") (pintype "power_in"))
      (node (ref "C1") (pin "2") (pinfunction "2_2") (pintype "passive"))
      (node (ref "C10") (pin "2") (pinfunction "2_2") (pintype "passive"))
      (node (ref "C11") (pin "2") (pinfunction "2_2") (pintype "passive"))
      (node (ref "C2") (pin "-") (pinfunction "-_-") (pintype "passive"))
      (node (ref "C3") (pin "2") (pinfunction "2_2") (pintype "passive"))
      (node (ref "C4") (pin "2") (pinfunction "2_2") (pintype "passive"))
      (node (ref "C5") (pin "2") (pinfunction "2_2") (pintype "passive"))
      (node (ref "C6") (pin "2") (pinfunction "2_2") (pintype "passive"))
      (node (ref "C7") (pin "2") (pinfunction "2_2") (pintype "passive"))
      (node (ref "C8") (pin "2") (pinfunction "2_2") (pintype "passive"))
      (node (ref "C9") (pin "2") (pinfunction "2_2") (pintype "passive"))
      (node (ref "D1") (pin "A") (pinfunction "A_A") (pintype "passive"))
      (node (ref "IC1") (pin "6") (pinfunction "INH_6") (pintype "input"))
      (node (ref "IC1") (pin "8") (pinfunction "GND_8") (pintype "power_in"))
      (node (ref "IC10") (pin "2") (pinfunction "GNDSIG_2") (pintype "input"))
      (node (ref "IC10") (pin "3") (pinfunction "~{ON/OFF}_3") (pintype "input"))
      (node (ref "IC10") (pin "4") (pinfunction "GND_4") (pintype "power_in"))
      (node (ref "IC3") (pin "13") (pinfunction "G_13") (pintype "input"))
      (node (ref "IC3") (pin "8") (pinfunction "GND_8") (pintype "power_in"))
      (node (ref "IC4") (pin "6") (pinfunction "INH_6") (pintype "input"))
      (node (ref "IC4") (pin "8") (pinfunction "GND_8") (pintype "power_in"))
      (node (ref "IC5") (pin "13") (pinfunction "G_13") (pintype "input"))
      (node (ref "IC5") (pin "8") (pinfunction "GND_8") (pintype "power_in"))
      (node (ref "IC6") (pin "11") (pinfunction "V-_11") (pintype "power_in"))
      (node (ref "IC7") (pin "2") (pinfunction "GND_2") (pintype "power_in"))
      (node (ref "IC9") (pin "11") (pinfunction "V-_11") (pintype "power_in"))
      (node (ref "J1") (pin "3") (pinfunction "3_3") (pintype "passive"))
      (node (ref "J1") (pin "6") (pinfunction "6_6") (pintype "passive"))
      (node (ref "J1") (pin "7") (pinfunction "7_7") (pintype "passive"))
      (node (ref "J2") (pin "3") (pinfunction "3_3") (pintype "passive"))
      (node (ref "J2") (pin "6") (pinfunction "6_6") (pintype "passive"))
      (node (ref "J2") (pin "7") (pinfunction "7_7") (pintype "passive"))
      (node (ref "J3") (pin "1") (pinfunction "1_1") (pintype "passive"))
      (node (ref "JP10") (pin "4") (pinfunction "4_4") (pintype "passive"))
      (node (ref "JP11") (pin "5") (pinfunction "5_5") (pintype "passive"))
      (node (ref "JP11") (pin "6") (pinfunction "6_6") (pintype "passive"))
      (node (ref "JP12") (pin "5") (pinfunction "5_5") (pintype "passive"))
      (node (ref "JP12") (pin "6") (pinfunction "6_6") (pintype "passive"))
      (node (ref "JP13") (pin "5") (pinfunction "5_5") (pintype "passive"))
      (node (ref "JP14") (pin "5") (pinfunction "5_5") (pintype "passive"))
      (node (ref "JP15") (pin "5") (pinfunction "5_5") (pintype "passive"))
      (node (ref "JP16") (pin "5") (pinfunction "5_5") (pintype "passive"))
      (node (ref "JP16") (pin "6") (pinfunction "6_6") (pintype "passive"))
      (node (ref "JP7") (pin "5") (pinfunction "5_5") (pintype "passive"))
      (node (ref "JP7") (pin "6") (pinfunction "6_6") (pintype "passive"))
      (node (ref "JP8") (pin "4") (pinfunction "4_4") (pintype "passive"))
      (node (ref "Q1") (pin "2") (pinfunction "S_2") (pintype "passive"))
      (node (ref "Q10") (pin "2") (pinfunction "S_2") (pintype "passive"))
      (node (ref "Q11") (pin "2") (pinfunction "S_2") (pintype "passive"))
      (node (ref "Q12") (pin "2") (pinfunction "S_2") (pintype "passive"))
      (node (ref "Q13") (pin "2") (pinfunction "S_2") (pintype "passive"))
      (node (ref "Q14") (pin "2") (pinfunction "S_2") (pintype "passive"))
      (node (ref "Q15") (pin "2") (pinfunction "S_2") (pintype "passive"))
      (node (ref "Q16") (pin "2") (pinfunction "S_2") (pintype "passive"))
      (node (ref "Q2") (pin "2") (pinfunction "S_2") (pintype "passive"))
      (node (ref "Q3") (pin "2") (pinfunction "S_2") (pintype "passive"))
      (node (ref "Q4") (pin "2") (pinfunction "S_2") (pintype "passive"))
      (node (ref "Q5") (pin "2") (pinfunction "S_2") (pintype "passive"))
      (node (ref "Q6") (pin "2") (pinfunction "S_2") (pintype "passive"))
      (node (ref "Q7") (pin "2") (pinfunction "S_2") (pintype "passive"))
      (node (ref "Q8") (pin "2") (pinfunction "S_2") (pintype "passive"))
      (node (ref "Q9") (pin "2") (pinfunction "S_2") (pintype "passive"))
      (node (ref "R2") (pin "1") (pinfunction "1_1") (pintype "passive"))
      (node (ref "R61") (pin "2") (pinfunction "2_2") (pintype "passive"))
      (node (ref "SJ12") (pin "P$2") (pinfunction "2_P$2") (pintype "passive"))
      (node (ref "SJ3") (pin "2") (pinfunction "2_2") (pintype "passive"))
      (node (ref "SJ6") (pin "P$2") (pinfunction "2_P$2") (pintype "passive"))
      (node (ref "SJ9") (pin "2") (pinfunction "2_2") (pintype "passive"))
      (node (ref "U$1") (pin "GND3") (pinfunction "GND3_GND3") (pintype "power_in"))
      (node (ref "U$1") (pin "GND5") (pinfunction "GND5_GND5") (pintype "power_in"))
      (node (ref "U$1") (pin "GND6") (pinfunction "GND6_GND6") (pintype "power_in"))
      (node (ref "U$1") (pin "GND7") (pinfunction "GND7_GND7") (pintype "power_in"))
      (node (ref "U$1") (pin "GND8") (pinfunction "GND8_GND8") (pintype "power_in"))
      (node (ref "U$2") (pin "3") (pinfunction "VSS_3") (pintype "power_in"))
      (node (ref "U$3") (pin "3") (pinfunction "VSS_3") (pintype "power_in"))
      (node (ref "U$4") (pin "3") (pinfunction "VSS_3") (pintype "power_in"))
      (node (ref "U$5") (pin "3") (pinfunction "VSS_3") (pintype "power_in"))
      (node (ref "U$6") (pin "2") (pinfunction "VSS_2") (pintype "power_in"))
      (node (ref "X1") (pin "2") (pinfunction "2_2") (pintype "passive"))
    )
    (net (code "17") (name "I2CSCL") (class "Default")
      (node (ref "JP8") (pin "2") (pinfunction "2_2") (pintype "passive"))
      (node (ref "R63") (pin "2") (pinfunction "2_2") (pintype "passive"))
      (node (ref "U$1") (pin "PB6") (pinfunction "PB6_PB6") (pintype "bidirectional"))
    )
    (net (code "18") (name "I2CSDA") (class "Default")
      (node (ref "JP8") (pin "1") (pinfunction "1_1") (pintype "passive"))
      (node (ref "R62") (pin "2") (pinfunction "2_2") (pintype "passive"))
      (node (ref "U$1") (pin "PB7") (pinfunction "PB7_PB7") (pintype "bidirectional"))
    )
    (net (code "19") (name "ILAT") (class "Default")
      (node (ref "IC1") (pin "15") (pinfunction "SH/~{LD}_15") (pintype "input"))
      (node (ref "IC4") (pin "15") (pinfunction "SH/~{LD}_15") (pintype "input"))
      (node (ref "U$1") (pin "PA6") (pinfunction "PA6_PA6") (pintype "bidirectional"))
    )
    (net (code "20") (name "MISO") (class "Default")
      (node (ref "JP9") (pin "1") (pinfunction "1_1") (pintype "passive"))
      (node (ref "U$1") (pin "PB4") (pinfunction "PB4_PB4") (pintype "bidirectional"))
    )
    (net (code "21") (name "MISO2") (class "Default")
      (node (ref "IC4") (pin "13") (pinfunction "QH_13") (pintype "output"))
      (node (ref "SJ13") (pin "P$2") (pinfunction "2_P$2") (pintype "passive"))
      (node (ref "U$1") (pin "PC2") (pinfunction "PC2_PC2") (pintype "bidirectional"))
    )
    (net (code "22") (name "MOSI") (class "Default")
      (node (ref "IC5") (pin "14") (pinfunction "SER_14") (pintype "input"))
      (node (ref "R20") (pin "1") (pinfunction "1_1") (pintype "passive"))
      (node (ref "SJ15") (pin "1") (pinfunction "1_1") (pintype "passive"))
      (node (ref "SJ17") (pin "P$2") (pinfunction "2_P$2") (pintype "passive"))
      (node (ref "U$1") (pin "PB5") (pinfunction "PB5_PB5") (pintype "bidirectional"))
    )
    (net (code "23") (name "Net-(AP1509-VOUT)") (class "Default")
      (node (ref "AP1509") (pin "2") (pinfunction "VOUT_2") (pintype "bidirectional"))
      (node (ref "D1") (pin "C") (pinfunction "C_C") (pintype "passive"))
      (node (ref "IC10") (pin "7") (pinfunction "OUT_7") (pintype "passive"))
      (node (ref "L1") (pin "2") (pinfunction "2_2") (pintype "passive"))
    )
    (net (code "24") (name "Net-(D2-PadA)") (class "Default")
      (node (ref "D2") (pin "A") (pinfunction "A_A") (pintype "passive"))
      (node (ref "JP4") (pin "4") (pinfunction "4_4") (pintype "passive"))
    )
    (net (code "25") (name "Net-(D2-PadC)") (class "Default")
      (node (ref "D2") (pin "C") (pinfunction "C_C") (pintype "passive"))
      (node (ref "JP4") (pin "1") (pinfunction "1_1") (pintype "passive"))
    )
    (net (code "26") (name "Net-(IC1A-A)") (class "Default")
      (node (ref "IC1") (pin "2") (pinfunction "A_2") (pintype "input"))
      (node (ref "R36") (pin "1") (pinfunction "1_1") (pintype "passive"))
      (node (ref "RN4") (pin "9") (pinfunction "2_9") (pintype "passive"))
    )
    (net (code "27") (name "Net-(IC1A-B)") (class "Default")
      (node (ref "IC1") (pin "3") (pinfunction "B_3") (pintype "input"))
      (node (ref "R37") (pin "1") (pinfunction "1_1") (pintype "passive"))
      (node (ref "RN4") (pin "10") (pinfunction "2_10") (pintype "passive"))
    )
    (net (code "28") (name "Net-(IC1A-C)") (class "Default")
      (node (ref "IC1") (pin "4") (pinfunction "C_4") (pintype "input"))
      (node (ref "R38") (pin "1") (pinfunction "1_1") (pintype "passive"))
      (node (ref "RN4") (pin "11") (pinfunction "2_11") (pintype "passive"))
    )
    (net (code "29") (name "Net-(IC1A-D)") (class "Default")
      (node (ref "IC1") (pin "5") (pinfunction "D_5") (pintype "input"))
      (node (ref "R39") (pin "1") (pinfunction "1_1") (pintype "passive"))
      (node (ref "RN4") (pin "12") (pinfunction "2_12") (pintype "passive"))
    )
    (net (code "30") (name "Net-(IC1A-E)") (class "Default")
      (node (ref "IC1") (pin "10") (pinfunction "E_10") (pintype "input"))
      (node (ref "R41") (pin "1") (pinfunction "1_1") (pintype "passive"))
      (node (ref "RN4") (pin "13") (pinfunction "2_13") (pintype "passive"))
    )
    (net (code "31") (name "Net-(IC1A-F)") (class "Default")
      (node (ref "IC1") (pin "11") (pinfunction "F_11") (pintype "input"))
      (node (ref "R42") (pin "1") (pinfunction "1_1") (pintype "passive"))
      (node (ref "RN4") (pin "14") (pinfunction "2_14") (pintype "passive"))
    )
    (net (code "32") (name "Net-(IC1A-G)") (class "Default")
      (node (ref "IC1") (pin "12") (pinfunction "G_12") (pintype "input"))
      (node (ref "R43") (pin "1") (pinfunction "1_1") (pintype "passive"))
      (node (ref "RN4") (pin "15") (pinfunction "2_15") (pintype "passive"))
    )
    (net (code "33") (name "Net-(IC1A-H)") (class "Default")
      (node (ref "IC1") (pin "14") (pinfunction "H_14") (pintype "input"))
      (node (ref "R44") (pin "1") (pinfunction "1_1") (pintype "passive"))
      (node (ref "RN4") (pin "16") (pinfunction "2_16") (pintype "passive"))
    )
    (net (code "34") (name "Net-(IC2-CD+)") (class "Default")
      (node (ref "IC2") (pin "10") (pinfunction "CD+_10") (pintype "passive"))
      (node (ref "SJ4") (pin "P$1") (pinfunction "1_P$1") (pintype "passive"))
      (node (ref "SJ5") (pin "P$1") (pinfunction "1_P$1") (pintype "passive"))
      (node (ref "SJ6") (pin "P$1") (pinfunction "1_P$1") (pintype "passive"))
    )
    (net (code "35") (name "Net-(IC2-GND)") (class "Default")
      (node (ref "IC2") (pin "9") (pinfunction "GND_9") (pintype "power_in"))
      (node (ref "SJ1") (pin "P$1") (pinfunction "1_P$1") (pintype "passive"))
      (node (ref "SJ2") (pin "P$1") (pinfunction "1_P$1") (pintype "passive"))
      (node (ref "SJ3") (pin "1") (pinfunction "1_1") (pintype "passive"))
    )
    (net (code "36") (name "Net-(IC2-I1)") (class "Default")
      (node (ref "IC2") (pin "1") (pinfunction "I1_1") (pintype "input"))
      (node (ref "IC5") (pin "15") (pinfunction "QA_15") (pintype "tri_state"))
      (node (ref "R3") (pin "1") (pinfunction "1_1") (pintype "passive"))
    )
    (net (code "37") (name "Net-(IC2-I2)") (class "Default")
      (node (ref "IC2") (pin "2") (pinfunction "I2_2") (pintype "input"))
      (node (ref "IC5") (pin "1") (pinfunction "QB_1") (pintype "tri_state"))
      (node (ref "R4") (pin "1") (pinfunction "1_1") (pintype "passive"))
    )
    (net (code "38") (name "Net-(IC2-I3)") (class "Default")
      (node (ref "IC2") (pin "3") (pinfunction "I3_3") (pintype "input"))
      (node (ref "IC5") (pin "2") (pinfunction "QC_2") (pintype "tri_state"))
      (node (ref "R5") (pin "1") (pinfunction "1_1") (pintype "passive"))
    )
    (net (code "39") (name "Net-(IC2-I4)") (class "Default")
      (node (ref "IC2") (pin "4") (pinfunction "I4_4") (pintype "input"))
      (node (ref "IC5") (pin "3") (pinfunction "QD_3") (pintype "tri_state"))
      (node (ref "R6") (pin "1") (pinfunction "1_1") (pintype "passive"))
    )
    (net (code "40") (name "Net-(IC2-I5)") (class "Default")
      (node (ref "IC2") (pin "5") (pinfunction "I5_5") (pintype "input"))
      (node (ref "IC5") (pin "4") (pinfunction "QE_4") (pintype "tri_state"))
      (node (ref "R7") (pin "1") (pinfunction "1_1") (pintype "passive"))
    )
    (net (code "41") (name "Net-(IC2-I6)") (class "Default")
      (node (ref "IC2") (pin "6") (pinfunction "I6_6") (pintype "input"))
      (node (ref "IC5") (pin "5") (pinfunction "QF_5") (pintype "tri_state"))
      (node (ref "R8") (pin "1") (pinfunction "1_1") (pintype "passive"))
    )
    (net (code "42") (name "Net-(IC2-I7)") (class "Default")
      (node (ref "IC2") (pin "7") (pinfunction "I7_7") (pintype "input"))
      (node (ref "IC5") (pin "6") (pinfunction "QG_6") (pintype "tri_state"))
      (node (ref "R9") (pin "1") (pinfunction "1_1") (pintype "passive"))
    )
    (net (code "43") (name "Net-(IC2-I8)") (class "Default")
      (node (ref "IC2") (pin "8") (pinfunction "I8_8") (pintype "input"))
      (node (ref "IC5") (pin "7") (pinfunction "QH_7") (pintype "tri_state"))
      (node (ref "R10") (pin "1") (pinfunction "1_1") (pintype "passive"))
    )
    (net (code "44") (name "Net-(IC2-O1)") (class "Default")
      (node (ref "IC2") (pin "18") (pinfunction "O1_18") (pintype "open_collector"))
      (node (ref "JP1") (pin "1") (pinfunction "1_1") (pintype "passive"))
      (node (ref "Q1") (pin "3") (pinfunction "D_3") (pintype "passive"))
    )
    (net (code "45") (name "Net-(IC2-O2)") (class "Default")
      (node (ref "IC2") (pin "17") (pinfunction "O2_17") (pintype "open_collector"))
      (node (ref "JP1") (pin "2") (pinfunction "2_2") (pintype "passive"))
      (node (ref "Q2") (pin "3") (pinfunction "D_3") (pintype "passive"))
    )
    (net (code "46") (name "Net-(IC2-O3)") (class "Default")
      (node (ref "IC2") (pin "16") (pinfunction "O3_16") (pintype "open_collector"))
      (node (ref "JP1") (pin "3") (pinfunction "3_3") (pintype "passive"))
      (node (ref "Q3") (pin "3") (pinfunction "D_3") (pintype "passive"))
    )
    (net (code "47") (name "Net-(IC2-O4)") (class "Default")
      (node (ref "IC2") (pin "15") (pinfunction "O4_15") (pintype "open_collector"))
      (node (ref "JP1") (pin "4") (pinfunction "4_4") (pintype "passive"))
      (node (ref "Q4") (pin "3") (pinfunction "D_3") (pintype "passive"))
    )
    (net (code "48") (name "Net-(IC2-O5)") (class "Default")
      (node (ref "IC2") (pin "14") (pinfunction "O5_14") (pintype "open_collector"))
      (node (ref "JP1") (pin "5") (pinfunction "5_5") (pintype "passive"))
      (node (ref "Q5") (pin "3") (pinfunction "D_3") (pintype "passive"))
    )
    (net (code "49") (name "Net-(IC2-O6)") (class "Default")
      (node (ref "IC2") (pin "13") (pinfunction "O6_13") (pintype "open_collector"))
      (node (ref "JP1") (pin "6") (pinfunction "6_6") (pintype "passive"))
      (node (ref "Q6") (pin "3") (pinfunction "D_3") (pintype "passive"))
    )
    (net (code "50") (name "Net-(IC2-O7)") (class "Default")
      (node (ref "IC2") (pin "12") (pinfunction "O7_12") (pintype "open_collector"))
      (node (ref "JP1") (pin "7") (pinfunction "7_7") (pintype "passive"))
      (node (ref "Q7") (pin "3") (pinfunction "D_3") (pintype "passive"))
    )
    (net (code "51") (name "Net-(IC2-O8)") (class "Default")
      (node (ref "IC2") (pin "11") (pinfunction "O8_11") (pintype "open_collector"))
      (node (ref "JP1") (pin "8") (pinfunction "8_8") (pintype "passive"))
      (node (ref "Q8") (pin "3") (pinfunction "D_3") (pintype "passive"))
    )
    (net (code "52") (name "Net-(IC3A-QA)") (class "Default")
      (node (ref "IC3") (pin "15") (pinfunction "QA_15") (pintype "tri_state"))
      (node (ref "IC8") (pin "1") (pinfunction "I1_1") (pintype "input"))
      (node (ref "R11") (pin "1") (pinfunction "1_1") (pintype "passive"))
    )
    (net (code "53") (name "Net-(IC3A-QB)") (class "Default")
      (node (ref "IC3") (pin "1") (pinfunction "QB_1") (pintype "tri_state"))
      (node (ref "IC8") (pin "2") (pinfunction "I2_2") (pintype "input"))
      (node (ref "R12") (pin "1") (pinfunction "1_1") (pintype "passive"))
    )
    (net (code "54") (name "Net-(IC3A-QC)") (class "Default")
      (node (ref "IC3") (pin "2") (pinfunction "QC_2") (pintype "tri_state"))
      (node (ref "IC8") (pin "3") (pinfunction "I3_3") (pintype "input"))
      (node (ref "R13") (pin "1") (pinfunction "1_1") (pintype "passive"))
    )
    (net (code "55") (name "Net-(IC3A-QD)") (class "Default")
      (node (ref "IC3") (pin "3") (pinfunction "QD_3") (pintype "tri_state"))
      (node (ref "IC8") (pin "4") (pinfunction "I4_4") (pintype "input"))
      (node (ref "R14") (pin "1") (pinfunction "1_1") (pintype "passive"))
    )
    (net (code "56") (name "Net-(IC3A-QE)") (class "Default")
      (node (ref "IC3") (pin "4") (pinfunction "QE_4") (pintype "tri_state"))
      (node (ref "IC8") (pin "5") (pinfunction "I5_5") (pintype "input"))
      (node (ref "R15") (pin "1") (pinfunction "1_1") (pintype "passive"))
    )
    (net (code "57") (name "Net-(IC3A-QF)") (class "Default")
      (node (ref "IC3") (pin "5") (pinfunction "QF_5") (pintype "tri_state"))
      (node (ref "IC8") (pin "6") (pinfunction "I6_6") (pintype "input"))
      (node (ref "R16") (pin "1") (pinfunction "1_1") (pintype "passive"))
    )
    (net (code "58") (name "Net-(IC3A-QG)") (class "Default")
      (node (ref "IC3") (pin "6") (pinfunction "QG_6") (pintype "tri_state"))
      (node (ref "IC8") (pin "7") (pinfunction "I7_7") (pintype "input"))
      (node (ref "R17") (pin "1") (pinfunction "1_1") (pintype "passive"))
    )
    (net (code "59") (name "Net-(IC3A-QH)") (class "Default")
      (node (ref "IC3") (pin "7") (pinfunction "QH_7") (pintype "tri_state"))
      (node (ref "IC8") (pin "8") (pinfunction "I8_8") (pintype "input"))
      (node (ref "R18") (pin "1") (pinfunction "1_1") (pintype "passive"))
    )
    (net (code "60") (name "Net-(IC4A-A)") (class "Default")
      (node (ref "IC4") (pin "2") (pinfunction "A_2") (pintype "input"))
      (node (ref "R28") (pin "1") (pinfunction "1_1") (pintype "passive"))
      (node (ref "RN1") (pin "9") (pinfunction "2_9") (pintype "passive"))
    )
    (net (code "61") (name "Net-(IC4A-B)") (class "Default")
      (node (ref "IC4") (pin "3") (pinfunction "B_3") (pintype "input"))
      (node (ref "R29") (pin "1") (pinfunction "1_1") (pintype "passive"))
      (node (ref "RN1") (pin "10") (pinfunction "2_10") (pintype "passive"))
    )
    (net (code "62") (name "Net-(IC4A-C)") (class "Default")
      (node (ref "IC4") (pin "4") (pinfunction "C_4") (pintype "input"))
      (node (ref "R30") (pin "1") (pinfunction "1_1") (pintype "passive"))
      (node (ref "RN1") (pin "11") (pinfunction "2_11") (pintype "passive"))
    )
    (net (code "63") (name "Net-(IC4A-D)") (class "Default")
      (node (ref "IC4") (pin "5") (pinfunction "D_5") (pintype "input"))
      (node (ref "R31") (pin "1") (pinfunction "1_1") (pintype "passive"))
      (node (ref "RN1") (pin "12") (pinfunction "2_12") (pintype "passive"))
    )
    (net (code "64") (name "Net-(IC4A-E)") (class "Default")
      (node (ref "IC4") (pin "10") (pinfunction "E_10") (pintype "input"))
      (node (ref "R32") (pin "1") (pinfunction "1_1") (pintype "passive"))
      (node (ref "RN1") (pin "13") (pinfunction "2_13") (pintype "passive"))
    )
    (net (code "65") (name "Net-(IC4A-F)") (class "Default")
      (node (ref "IC4") (pin "11") (pinfunction "F_11") (pintype "input"))
      (node (ref "R33") (pin "1") (pinfunction "1_1") (pintype "passive"))
      (node (ref "RN1") (pin "14") (pinfunction "2_14") (pintype "passive"))
    )
    (net (code "66") (name "Net-(IC4A-G)") (class "Default")
      (node (ref "IC4") (pin "12") (pinfunction "G_12") (pintype "input"))
      (node (ref "R34") (pin "1") (pinfunction "1_1") (pintype "passive"))
      (node (ref "RN1") (pin "15") (pinfunction "2_15") (pintype "passive"))
    )
    (net (code "67") (name "Net-(IC4A-H)") (class "Default")
      (node (ref "IC4") (pin "14") (pinfunction "H_14") (pintype "input"))
      (node (ref "R35") (pin "1") (pinfunction "1_1") (pintype "passive"))
      (node (ref "RN1") (pin "16") (pinfunction "2_16") (pintype "passive"))
    )
    (net (code "68") (name "Net-(IC6A--IN)") (class "Default")
      (node (ref "IC6") (pin "13") (pinfunction "-IN_13") (pintype "input"))
      (node (ref "IC6") (pin "2") (pinfunction "-IN_2") (pintype "input"))
      (node (ref "IC6") (pin "6") (pinfunction "-IN_6") (pintype "input"))
      (node (ref "IC6") (pin "9") (pinfunction "-IN_9") (pintype "input"))
      (node (ref "IC9") (pin "13") (pinfunction "-IN_13") (pintype "input"))
      (node (ref "IC9") (pin "2") (pinfunction "-IN_2") (pintype "input"))
      (node (ref "IC9") (pin "6") (pinfunction "-IN_6") (pintype "input"))
      (node (ref "IC9") (pin "9") (pinfunction "-IN_9") (pintype "input"))
      (node (ref "R1") (pin "1") (pinfunction "1_1") (pintype "passive"))
      (node (ref "R2") (pin "2") (pinfunction "2_2") (pintype "passive"))
    )
    (net (code "69") (name "Net-(IC6A-OUT)") (class "Default")
      (node (ref "IC6") (pin "1") (pinfunction "OUT_1") (pintype "output"))
      (node (ref "JP15") (pin "3") (pinfunction "3_3") (pintype "passive"))
      (node (ref "JP5") (pin "3") (pinfunction "3_3") (pintype "passive"))
      (node (ref "U$5") (pin "5") (pinfunction "O_5") (pintype "output"))
    )
    (net (code "70") (name "Net-(IC6B-OUT)") (class "Default")
      (node (ref "IC6") (pin "7") (pinfunction "OUT_7") (pintype "output"))
      (node (ref "JP15") (pin "1") (pinfunction "1_1") (pintype "passive"))
      (node (ref "JP5") (pin "1") (pinfunction "1_1") (pintype "passive"))
      (node (ref "U$4") (pin "7") (pinfunction "O_7") (pintype "output"))
    )
    (net (code "71") (name "Net-(IC6C-OUT)") (class "Default")
      (node (ref "IC6") (pin "8") (pinfunction "OUT_8") (pintype "output"))
      (node (ref "JP15") (pin "2") (pinfunction "2_2") (pintype "passive"))
      (node (ref "JP5") (pin "2") (pinfunction "2_2") (pintype "passive"))
      (node (ref "U$4") (pin "5") (pinfunction "O_5") (pintype "output"))
    )
    (net (code "72") (name "Net-(IC6D-OUT)") (class "Default")
      (node (ref "IC6") (pin "14") (pinfunction "OUT_14") (pintype "output"))
      (node (ref "JP15") (pin "4") (pinfunction "4_4") (pintype "passive"))
      (node (ref "JP5") (pin "4") (pinfunction "4_4") (pintype "passive"))
      (node (ref "U$5") (pin "7") (pinfunction "O_7") (pintype "output"))
    )
    (net (code "73") (name "Net-(IC7-RS)") (class "Default")
      (node (ref "IC7") (pin "8") (pinfunction "RS_8") (pintype "input"))
      (node (ref "R61") (pin "1") (pinfunction "1_1") (pintype "passive"))
      (node (ref "U$6") (pin "8") (pinfunction "RS_8") (pintype "bidirectional"))
    )
    (net (code "74") (name "Net-(IC7-VREF)") (class "Default")
      (node (ref "IC7") (pin "5") (pinfunction "VREF_5") (pintype "output"))
      (node (ref "SJ18") (pin "P$2") (pinfunction "2_P$2") (pintype "passive"))
      (node (ref "U$6") (pin "5") (pinfunction "VREF_5") (pintype "bidirectional"))
    )
    (net (code "75") (name "Net-(IC8-CD+)") (class "Default")
      (node (ref "IC8") (pin "10") (pinfunction "CD+_10") (pintype "passive"))
      (node (ref "SJ10") (pin "P$1") (pinfunction "1_P$1") (pintype "passive"))
      (node (ref "SJ11") (pin "P$1") (pinfunction "1_P$1") (pintype "passive"))
      (node (ref "SJ12") (pin "P$1") (pinfunction "1_P$1") (pintype "passive"))
    )
    (net (code "76") (name "Net-(IC8-GND)") (class "Default")
      (node (ref "IC8") (pin "9") (pinfunction "GND_9") (pintype "power_in"))
      (node (ref "SJ7") (pin "P$1") (pinfunction "1_P$1") (pintype "passive"))
      (node (ref "SJ8") (pin "P$1") (pinfunction "1_P$1") (pintype "passive"))
      (node (ref "SJ9") (pin "1") (pinfunction "1_1") (pintype "passive"))
    )
    (net (code "77") (name "Net-(IC8-O1)") (class "Default")
      (node (ref "IC8") (pin "18") (pinfunction "O1_18") (pintype "open_collector"))
      (node (ref "JP6") (pin "1") (pinfunction "1_1") (pintype "passive"))
      (node (ref "Q9") (pin "3") (pinfunction "D_3") (pintype "passive"))
    )
    (net (code "78") (name "Net-(IC8-O2)") (class "Default")
      (node (ref "IC8") (pin "17") (pinfunction "O2_17") (pintype "open_collector"))
      (node (ref "JP6") (pin "2") (pinfunction "2_2") (pintype "passive"))
      (node (ref "Q10") (pin "3") (pinfunction "D_3") (pintype "passive"))
    )
    (net (code "79") (name "Net-(IC8-O3)") (class "Default")
      (node (ref "IC8") (pin "16") (pinfunction "O3_16") (pintype "open_collector"))
      (node (ref "JP6") (pin "3") (pinfunction "3_3") (pintype "passive"))
      (node (ref "Q11") (pin "3") (pinfunction "D_3") (pintype "passive"))
    )
    (net (code "80") (name "Net-(IC8-O4)") (class "Default")
      (node (ref "IC8") (pin "15") (pinfunction "O4_15") (pintype "open_collector"))
      (node (ref "JP6") (pin "4") (pinfunction "4_4") (pintype "passive"))
      (node (ref "Q12") (pin "3") (pinfunction "D_3") (pintype "passive"))
    )
    (net (code "81") (name "Net-(IC8-O5)") (class "Default")
      (node (ref "IC8") (pin "14") (pinfunction "O5_14") (pintype "open_collector"))
      (node (ref "JP6") (pin "5") (pinfunction "5_5") (pintype "passive"))
      (node (ref "Q13") (pin "3") (pinfunction "D_3") (pintype "passive"))
    )
    (net (code "82") (name "Net-(IC8-O6)") (class "Default")
      (node (ref "IC8") (pin "13") (pinfunction "O6_13") (pintype "open_collector"))
      (node (ref "JP6") (pin "6") (pinfunction "6_6") (pintype "passive"))
      (node (ref "Q14") (pin "3") (pinfunction "D_3") (pintype "passive"))
    )
    (net (code "83") (name "Net-(IC8-O7)") (class "Default")
      (node (ref "IC8") (pin "12") (pinfunction "O7_12") (pintype "open_collector"))
      (node (ref "JP6") (pin "7") (pinfunction "7_7") (pintype "passive"))
      (node (ref "Q15") (pin "3") (pinfunction "D_3") (pintype "passive"))
    )
    (net (code "84") (name "Net-(IC8-O8)") (class "Default")
      (node (ref "IC8") (pin "11") (pinfunction "O8_11") (pintype "open_collector"))
      (node (ref "JP6") (pin "8") (pinfunction "8_8") (pintype "passive"))
      (node (ref "Q16") (pin "3") (pinfunction "D_3") (pintype "passive"))
    )
    (net (code "85") (name "Net-(IC9A-OUT)") (class "Default")
      (node (ref "IC9") (pin "1") (pinfunction "OUT_1") (pintype "output"))
      (node (ref "JP15") (pin "9") (pinfunction "9_9") (pintype "passive"))
      (node (ref "JP5") (pin "7") (pinfunction "7_7") (pintype "passive"))
      (node (ref "U$3") (pin "5") (pinfunction "O_5") (pintype "output"))
    )
    (net (code "86") (name "Net-(IC9B-OUT)") (class "Default")
      (node (ref "IC9") (pin "7") (pinfunction "OUT_7") (pintype "output"))
      (node (ref "JP15") (pin "7") (pinfunction "7_7") (pintype "passive"))
      (node (ref "JP5") (pin "5") (pinfunction "5_5") (pintype "passive"))
      (node (ref "U$2") (pin "7") (pinfunction "O_7") (pintype "output"))
    )
    (net (code "87") (name "Net-(IC9C-OUT)") (class "Default")
      (node (ref "IC9") (pin "8") (pinfunction "OUT_8") (pintype "output"))
      (node (ref "JP15") (pin "8") (pinfunction "8_8") (pintype "passive"))
      (node (ref "JP5") (pin "6") (pinfunction "6_6") (pintype "passive"))
      (node (ref "U$2") (pin "5") (pinfunction "O_5") (pintype "output"))
    )
    (net (code "88") (name "Net-(IC9D-OUT)") (class "Default")
      (node (ref "IC9") (pin "14") (pinfunction "OUT_14") (pintype "output"))
      (node (ref "JP15") (pin "10") (pinfunction "10_10") (pintype "passive"))
      (node (ref "JP5") (pin "8") (pinfunction "8_8") (pintype "passive"))
      (node (ref "U$3") (pin "7") (pinfunction "O_7") (pintype "output"))
    )
    (net (code "89") (name "Net-(J1-Pad4)") (class "Default")
      (node (ref "J1") (pin "4") (pinfunction "4_4") (pintype "passive"))
      (node (ref "J2") (pin "4") (pinfunction "4_4") (pintype "passive"))
    )
    (net (code "90") (name "Net-(J1-Pad5)") (class "Default")
      (node (ref "J1") (pin "5") (pinfunction "5_5") (pintype "passive"))
      (node (ref "J2") (pin "5") (pinfunction "5_5") (pintype "passive"))
    )
    (net (code "91") (name "Net-(J1-Pad8)") (class "Default")
      (node (ref "J1") (pin "8") (pinfunction "8_8") (pintype "passive"))
      (node (ref "J2") (pin "8") (pinfunction "8_8") (pintype "passive"))
      (node (ref "R40") (pin "1") (pinfunction "1_1") (pintype "passive"))
    )
    (net (code "92") (name "Net-(JP4-Pad3)") (class "Default")
      (node (ref "JP4") (pin "3") (pinfunction "3_3") (pintype "passive"))
      (node (ref "R40") (pin "2") (pinfunction "2_2") (pintype "passive"))
    )
    (net (code "93") (name "Net-(JP13-Pad1)") (class "Default")
      (node (ref "JP13") (pin "1") (pinfunction "1_1") (pintype "passive"))
      (node (ref "JP3") (pin "1") (pinfunction "1_1") (pintype "passive"))
      (node (ref "R44") (pin "2") (pinfunction "2_2") (pintype "passive"))
      (node (ref "R53") (pin "2") (pinfunction "2_2") (pintype "passive"))
      (node (ref "RN4") (pin "1") (pinfunction "1_1") (pintype "passive"))
      (node (ref "RN5") (pin "9") (pinfunction "9_9") (pintype "passive"))
    )
    (net (code "94") (name "Net-(JP14-Pad1)") (class "Default")
      (node (ref "JP14") (pin "1") (pinfunction "1_1") (pintype "passive"))
      (node (ref "JP2") (pin "1") (pinfunction "1_1") (pintype "passive"))
      (node (ref "R35") (pin "2") (pinfunction "2_2") (pintype "passive"))
      (node (ref "R45") (pin "2") (pinfunction "2_2") (pintype "passive"))
      (node (ref "RN1") (pin "1") (pinfunction "1_1") (pintype "passive"))
      (node (ref "RN2") (pin "9") (pinfunction "9_9") (pintype "passive"))
    )
    (net (code "95") (name "Net-(Q1-G)") (class "Default")
      (node (ref "Q1") (pin "1") (pinfunction "G_1") (pintype "passive"))
      (node (ref "R3") (pin "2") (pinfunction "2_2") (pintype "passive"))
    )
    (net (code "96") (name "Net-(Q2-G)") (class "Default")
      (node (ref "Q2") (pin "1") (pinfunction "G_1") (pintype "passive"))
      (node (ref "R4") (pin "2") (pinfunction "2_2") (pintype "passive"))
    )
    (net (code "97") (name "Net-(Q3-G)") (class "Default")
      (node (ref "Q3") (pin "1") (pinfunction "G_1") (pintype "passive"))
      (node (ref "R5") (pin "2") (pinfunction "2_2") (pintype "passive"))
    )
    (net (code "98") (name "Net-(Q4-G)") (class "Default")
      (node (ref "Q4") (pin "1") (pinfunction "G_1") (pintype "passive"))
      (node (ref "R6") (pin "2") (pinfunction "2_2") (pintype "passive"))
    )
    (net (code "99") (name "Net-(Q5-G)") (class "Default")
      (node (ref "Q5") (pin "1") (pinfunction "G_1") (pintype "passive"))
      (node (ref "R7") (pin "2") (pinfunction "2_2") (pintype "passive"))
    )
    (net (code "100") (name "Net-(Q6-G)") (class "Default")
      (node (ref "Q6") (pin "1") (pinfunction "G_1") (pintype "passive"))
      (node (ref "R8") (pin "2") (pinfunction "2_2") (pintype "passive"))
    )
    (net (code "101") (name "Net-(Q7-G)") (class "Default")
      (node (ref "Q7") (pin "1") (pinfunction "G_1") (pintype "passive"))
      (node (ref "R9") (pin "2") (pinfunction "2_2") (pintype "passive"))
    )
    (net (code "102") (name "Net-(Q8-G)") (class "Default")
      (node (ref "Q8") (pin "1") (pinfunction "G_1") (pintype "passive"))
      (node (ref "R10") (pin "2") (pinfunction "2_2") (pintype "passive"))
    )
    (net (code "103") (name "Net-(Q9-G)") (class "Default")
      (node (ref "Q9") (pin "1") (pinfunction "G_1") (pintype "passive"))
      (node (ref "R11") (pin "2") (pinfunction "2_2") (pintype "passive"))
    )
    (net (code "104") (name "Net-(Q10-G)") (class "Default")
      (node (ref "Q10") (pin "1") (pinfunction "G_1") (pintype "passive"))
      (node (ref "R12") (pin "2") (pinfunction "2_2") (pintype "passive"))
    )
    (net (code "105") (name "Net-(Q11-G)") (class "Default")
      (node (ref "Q11") (pin "1") (pinfunction "G_1") (pintype "passive"))
      (node (ref "R13") (pin "2") (pinfunction "2_2") (pintype "passive"))
    )
    (net (code "106") (name "Net-(Q12-G)") (class "Default")
      (node (ref "Q12") (pin "1") (pinfunction "G_1") (pintype "passive"))
      (node (ref "R14") (pin "2") (pinfunction "2_2") (pintype "passive"))
    )
    (net (code "107") (name "Net-(Q13-G)") (class "Default")
      (node (ref "Q13") (pin "1") (pinfunction "G_1") (pintype "passive"))
      (node (ref "R15") (pin "2") (pinfunction "2_2") (pintype "passive"))
    )
    (net (code "108") (name "Net-(Q14-G)") (class "Default")
      (node (ref "Q14") (pin "1") (pinfunction "G_1") (pintype "passive"))
      (node (ref "R16") (pin "2") (pinfunction "2_2") (pintype "passive"))
    )
    (net (code "109") (name "Net-(Q15-G)") (class "Default")
      (node (ref "Q15") (pin "1") (pinfunction "G_1") (pintype "passive"))
      (node (ref "R17") (pin "2") (pinfunction "2_2") (pintype "passive"))
    )
    (net (code "110") (name "Net-(Q16-G)") (class "Default")
      (node (ref "Q16") (pin "1") (pinfunction "G_1") (pintype "passive"))
      (node (ref "R18") (pin "2") (pinfunction "2_2") (pintype "passive"))
    )
    (net (code "111") (name "Net-(RN1B-1)") (class "Default")
      (node (ref "JP14") (pin "2") (pinfunction "2_2") (pintype "passive"))
      (node (ref "JP2") (pin "2") (pinfunction "2_2") (pintype "passive"))
      (node (ref "R34") (pin "2") (pinfunction "2_2") (pintype "passive"))
      (node (ref "R46") (pin "1") (pinfunction "1_1") (pintype "passive"))
      (node (ref "RN1") (pin "2") (pinfunction "1_2") (pintype "passive"))
      (node (ref "RN2") (pin "8") (pinfunction "8_8") (pintype "passive"))
    )
    (net (code "112") (name "Net-(RN1C-1)") (class "Default")
      (node (ref "JP14") (pin "3") (pinfunction "3_3") (pintype "passive"))
      (node (ref "JP2") (pin "3") (pinfunction "3_3") (pintype "passive"))
      (node (ref "R33") (pin "2") (pinfunction "2_2") (pintype "passive"))
      (node (ref "R47") (pin "1") (pinfunction "1_1") (pintype "passive"))
      (node (ref "RN1") (pin "3") (pinfunction "1_3") (pintype "passive"))
      (node (ref "RN2") (pin "7") (pinfunction "7_7") (pintype "passive"))
    )
    (net (code "113") (name "Net-(RN1D-1)") (class "Default")
      (node (ref "JP14") (pin "4") (pinfunction "4_4") (pintype "passive"))
      (node (ref "JP2") (pin "4") (pinfunction "4_4") (pintype "passive"))
      (node (ref "R32") (pin "2") (pinfunction "2_2") (pintype "passive"))
      (node (ref "R48") (pin "1") (pinfunction "1_1") (pintype "passive"))
      (node (ref "RN1") (pin "4") (pinfunction "1_4") (pintype "passive"))
      (node (ref "RN2") (pin "6") (pinfunction "6_6") (pintype "passive"))
    )
    (net (code "114") (name "Net-(RN1E-1)") (class "Default")
      (node (ref "JP14") (pin "7") (pinfunction "7_7") (pintype "passive"))
      (node (ref "JP2") (pin "5") (pinfunction "5_5") (pintype "passive"))
      (node (ref "R31") (pin "2") (pinfunction "2_2") (pintype "passive"))
      (node (ref "R49") (pin "1") (pinfunction "1_1") (pintype "passive"))
      (node (ref "RN1") (pin "5") (pinfunction "1_5") (pintype "passive"))
      (node (ref "RN2") (pin "5") (pinfunction "5_5") (pintype "passive"))
    )
    (net (code "115") (name "Net-(RN1F-1)") (class "Default")
      (node (ref "JP14") (pin "8") (pinfunction "8_8") (pintype "passive"))
      (node (ref "JP2") (pin "6") (pinfunction "6_6") (pintype "passive"))
      (node (ref "R30") (pin "2") (pinfunction "2_2") (pintype "passive"))
      (node (ref "R50") (pin "1") (pinfunction "1_1") (pintype "passive"))
      (node (ref "RN1") (pin "6") (pinfunction "1_6") (pintype "passive"))
      (node (ref "RN2") (pin "4") (pinfunction "4_4") (pintype "passive"))
    )
    (net (code "116") (name "Net-(RN1G-1)") (class "Default")
      (node (ref "JP14") (pin "9") (pinfunction "9_9") (pintype "passive"))
      (node (ref "JP2") (pin "7") (pinfunction "7_7") (pintype "passive"))
      (node (ref "R29") (pin "2") (pinfunction "2_2") (pintype "passive"))
      (node (ref "R51") (pin "1") (pinfunction "1_1") (pintype "passive"))
      (node (ref "RN1") (pin "7") (pinfunction "1_7") (pintype "passive"))
      (node (ref "RN2") (pin "3") (pinfunction "3_3") (pintype "passive"))
    )
    (net (code "117") (name "Net-(RN1H-1)") (class "Default")
      (node (ref "JP14") (pin "10") (pinfunction "10_10") (pintype "passive"))
      (node (ref "JP2") (pin "8") (pinfunction "8_8") (pintype "passive"))
      (node (ref "R28") (pin "2") (pinfunction "2_2") (pintype "passive"))
      (node (ref "R52") (pin "1") (pinfunction "1_1") (pintype "passive"))
      (node (ref "RN1") (pin "8") (pinfunction "1_8") (pintype "passive"))
      (node (ref "RN2") (pin "2") (pinfunction "2_2") (pintype "passive"))
    )
    (net (code "118") (name "Net-(RN4B-1)") (class "Default")
      (node (ref "JP13") (pin "2") (pinfunction "2_2") (pintype "passive"))
      (node (ref "JP3") (pin "2") (pinfunction "2_2") (pintype "passive"))
      (node (ref "R43") (pin "2") (pinfunction "2_2") (pintype "passive"))
      (node (ref "R54") (pin "2") (pinfunction "2_2") (pintype "passive"))
      (node (ref "RN4") (pin "2") (pinfunction "1_2") (pintype "passive"))
      (node (ref "RN5") (pin "8") (pinfunction "8_8") (pintype "passive"))
    )
    (net (code "119") (name "Net-(RN4C-1)") (class "Default")
      (node (ref "JP13") (pin "3") (pinfunction "3_3") (pintype "passive"))
      (node (ref "JP3") (pin "3") (pinfunction "3_3") (pintype "passive"))
      (node (ref "R42") (pin "2") (pinfunction "2_2") (pintype "passive"))
      (node (ref "R55") (pin "2") (pinfunction "2_2") (pintype "passive"))
      (node (ref "RN4") (pin "3") (pinfunction "1_3") (pintype "passive"))
      (node (ref "RN5") (pin "7") (pinfunction "7_7") (pintype "passive"))
    )
    (net (code "120") (name "Net-(RN4D-1)") (class "Default")
      (node (ref "JP13") (pin "4") (pinfunction "4_4") (pintype "passive"))
      (node (ref "JP3") (pin "4") (pinfunction "4_4") (pintype "passive"))
      (node (ref "R41") (pin "2") (pinfunction "2_2") (pintype "passive"))
      (node (ref "R56") (pin "2") (pinfunction "2_2") (pintype "passive"))
      (node (ref "RN4") (pin "4") (pinfunction "1_4") (pintype "passive"))
      (node (ref "RN5") (pin "6") (pinfunction "6_6") (pintype "passive"))
    )
    (net (code "121") (name "Net-(RN4E-1)") (class "Default")
      (node (ref "JP13") (pin "7") (pinfunction "7_7") (pintype "passive"))
      (node (ref "JP3") (pin "5") (pinfunction "5_5") (pintype "passive"))
      (node (ref "R39") (pin "2") (pinfunction "2_2") (pintype "passive"))
      (node (ref "R57") (pin "2") (pinfunction "2_2") (pintype "passive"))
      (node (ref "RN4") (pin "5") (pinfunction "1_5") (pintype "passive"))
      (node (ref "RN5") (pin "5") (pinfunction "5_5") (pintype "passive"))
    )
    (net (code "122") (name "Net-(RN4F-1)") (class "Default")
      (node (ref "JP13") (pin "8") (pinfunction "8_8") (pintype "passive"))
      (node (ref "JP3") (pin "6") (pinfunction "6_6") (pintype "passive"))
      (node (ref "R38") (pin "2") (pinfunction "2_2") (pintype "passive"))
      (node (ref "R58") (pin "2") (pinfunction "2_2") (pintype "passive"))
      (node (ref "RN4") (pin "6") (pinfunction "1_6") (pintype "passive"))
      (node (ref "RN5") (pin "4") (pinfunction "4_4") (pintype "passive"))
    )
    (net (code "123") (name "Net-(RN4G-1)") (class "Default")
      (node (ref "JP13") (pin "9") (pinfunction "9_9") (pintype "passive"))
      (node (ref "JP3") (pin "7") (pinfunction "7_7") (pintype "passive"))
      (node (ref "R37") (pin "2") (pinfunction "2_2") (pintype "passive"))
      (node (ref "R59") (pin "2") (pinfunction "2_2") (pintype "passive"))
      (node (ref "RN4") (pin "7") (pinfunction "1_7") (pintype "passive"))
      (node (ref "RN5") (pin "3") (pinfunction "3_3") (pintype "passive"))
    )
    (net (code "124") (name "Net-(RN4H-1)") (class "Default")
      (node (ref "JP13") (pin "10") (pinfunction "10_10") (pintype "passive"))
      (node (ref "JP3") (pin "8") (pinfunction "8_8") (pintype "passive"))
      (node (ref "R36") (pin "2") (pinfunction "2_2") (pintype "passive"))
      (node (ref "R60") (pin "2") (pinfunction "2_2") (pintype "passive"))
      (node (ref "RN4") (pin "8") (pinfunction "1_8") (pintype "passive"))
      (node (ref "RN5") (pin "2") (pinfunction "2_2") (pintype "passive"))
    )
    (net (code "125") (name "Net-(SJ13-1)") (class "Default")
      (node (ref "SJ13") (pin "P$1") (pinfunction "1_P$1") (pintype "passive"))
      (node (ref "U$1") (pin "PB14") (pinfunction "PB14_PB14") (pintype "bidirectional"))
    )
    (net (code "126") (name "Net-(SJ14-1)") (class "Default")
      (node (ref "SJ14") (pin "P$1") (pinfunction "1_P$1") (pintype "passive"))
      (node (ref "U$1") (pin "VIN2") (pinfunction "VIN2_VIN2") (pintype "power_in"))
    )
    (net (code "127") (name "Net-(SJ16-2)") (class "Default")
      (node (ref "JP9") (pin "2") (pinfunction "2_2") (pintype "passive"))
      (node (ref "SJ15") (pin "2") (pinfunction "2_2") (pintype "passive"))
      (node (ref "SJ16") (pin "P$2") (pinfunction "2_P$2") (pintype "passive"))
    )
    (net (code "128") (name "OLAT") (class "Default")
      (node (ref "IC3") (pin "12") (pinfunction "RCK_12") (pintype "input"))
      (node (ref "IC5") (pin "12") (pinfunction "RCK_12") (pintype "input"))
      (node (ref "R21") (pin "1") (pinfunction "1_1") (pintype "passive"))
      (node (ref "U$1") (pin "PA8") (pinfunction "PA8_PA8") (pintype "bidirectional"))
    )
    (net (code "129") (name "SCK") (class "Default")
      (node (ref "IC3") (pin "11") (pinfunction "SCK_11") (pintype "input"))
      (node (ref "IC5") (pin "11") (pinfunction "SCK_11") (pintype "input"))
      (node (ref "JP9") (pin "3") (pinfunction "3_3") (pintype "passive"))
      (node (ref "R19") (pin "1") (pinfunction "1_1") (pintype "passive"))
      (node (ref "U$1") (pin "PB3") (pinfunction "PB3_PB3") (pintype "bidirectional"))
    )
    (net (code "130") (name "SCK2") (class "Default")
      (node (ref "IC1") (pin "7") (pinfunction "CLK_7") (pintype "input"))
      (node (ref "IC4") (pin "7") (pinfunction "CLK_7") (pintype "input"))
      (node (ref "U$1") (pin "PB10") (pinfunction "PB10_PB10") (pintype "bidirectional"))
    )
    (net (code "131") (name "SLNK1") (class "Default")
      (node (ref "IC3") (pin "14") (pinfunction "SER_14") (pintype "input"))
      (node (ref "IC5") (pin "9") (pinfunction "QH*_9") (pintype "tri_state"))
      (node (ref "SJ17") (pin "P$1") (pinfunction "1_P$1") (pintype "passive"))
    )
    (net (code "132") (name "SLNK2") (class "Default")
      (node (ref "IC3") (pin "9") (pinfunction "QH*_9") (pintype "tri_state"))
      (node (ref "SJ16") (pin "P$1") (pinfunction "1_P$1") (pintype "passive"))
    )
    (net (code "133") (name "SLNK3") (class "Default")
      (node (ref "IC1") (pin "13") (pinfunction "QH_13") (pintype "output"))
      (node (ref "IC4") (pin "1") (pinfunction "SER_1") (pintype "input"))
    )
    (net (code "134") (name "SRV1") (class "Default")
      (node (ref "JP7") (pin "2") (pinfunction "2_2") (pintype "passive"))
      (node (ref "R25") (pin "2") (pinfunction "2_2") (pintype "passive"))
      (node (ref "U$1") (pin "PC9") (pinfunction "PC9_PC9") (pintype "bidirectional"))
    )
    (net (code "135") (name "SRV2") (class "Default")
      (node (ref "JP7") (pin "1") (pinfunction "1_1") (pintype "passive"))
      (node (ref "R24") (pin "2") (pinfunction "2_2") (pintype "passive"))
      (node (ref "U$1") (pin "PC7") (pinfunction "PC7_PC7") (pintype "bidirectional"))
    )
    (net (code "136") (name "SRV3") (class "Default")
      (node (ref "JP11") (pin "2") (pinfunction "2_2") (pintype "passive"))
      (node (ref "R26") (pin "2") (pinfunction "2_2") (pintype "passive"))
      (node (ref "U$1") (pin "PC8") (pinfunction "PC8_PC8") (pintype "bidirectional"))
    )
    (net (code "137") (name "SRV4") (class "Default")
      (node (ref "JP11") (pin "1") (pinfunction "1_1") (pintype "passive"))
      (node (ref "R27") (pin "2") (pinfunction "2_2") (pintype "passive"))
      (node (ref "U$1") (pin "PC6") (pinfunction "PC6_PC6") (pintype "bidirectional"))
    )
    (net (code "138") (name "SRV5") (class "Default")
      (node (ref "JP12") (pin "2") (pinfunction "2_2") (pintype "passive"))
      (node (ref "R64") (pin "2") (pinfunction "2_2") (pintype "passive"))
      (node (ref "U$1") (pin "PF1-PH1") (pinfunction "PF1-PH1_PF1-PH1") (pintype "bidirectional"))
    )
    (net (code "139") (name "SRV6") (class "Default")
      (node (ref "JP12") (pin "1") (pinfunction "1_1") (pintype "passive"))
      (node (ref "R65") (pin "2") (pinfunction "2_2") (pintype "passive"))
      (node (ref "U$1") (pin "PA15") (pinfunction "PA15_PA15") (pintype "bidirectional"))
    )
    (net (code "140") (name "SRV7") (class "Default")
      (node (ref "JP16") (pin "2") (pinfunction "2_2") (pintype "passive"))
      (node (ref "R66") (pin "2") (pinfunction "2_2") (pintype "passive"))
      (node (ref "U$1") (pin "PC12") (pinfunction "PC12_PC12") (pintype "bidirectional"))
    )
    (net (code "141") (name "SRV8") (class "Default")
      (node (ref "JP16") (pin "1") (pinfunction "1_1") (pintype "passive"))
      (node (ref "R67") (pin "2") (pinfunction "2_2") (pintype "passive"))
      (node (ref "U$1") (pin "PD2") (pinfunction "PD2_PD2") (pintype "bidirectional"))
    )
    (net (code "142") (name "TIN1") (class "Default")
      (node (ref "IC9") (pin "3") (pinfunction "+IN_3") (pintype "input"))
      (node (ref "U$1") (pin "PB2") (pinfunction "PB2_PB2") (pintype "bidirectional"))
      (node (ref "U$3") (pin "4") (pinfunction "I_4") (pintype "input"))
    )
    (net (code "143") (name "TIN2") (class "Default")
      (node (ref "IC9") (pin "5") (pinfunction "+IN_5") (pintype "input"))
      (node (ref "U$1") (pin "PB1") (pinfunction "PB1_PB1") (pintype "bidirectional"))
      (node (ref "U$2") (pin "2") (pinfunction "I_2") (pintype "input"))
    )
    (net (code "144") (name "TIN3") (class "Default")
      (node (ref "IC9") (pin "10") (pinfunction "+IN_10") (pintype "input"))
      (node (ref "U$1") (pin "PB15") (pinfunction "PB15_PB15") (pintype "bidirectional"))
      (node (ref "U$2") (pin "4") (pinfunction "I_4") (pintype "input"))
    )
    (net (code "145") (name "TIN4") (class "Default")
      (node (ref "IC9") (pin "12") (pinfunction "+IN_12") (pintype "input"))
      (node (ref "U$1") (pin "PB12") (pinfunction "PB12_PB12") (pintype "bidirectional"))
      (node (ref "U$3") (pin "2") (pinfunction "I_2") (pintype "input"))
    )
    (net (code "146") (name "TIN5") (class "Default")
      (node (ref "IC6") (pin "3") (pinfunction "+IN_3") (pintype "input"))
      (node (ref "U$1") (pin "PA4") (pinfunction "PA4_PA4") (pintype "bidirectional"))
      (node (ref "U$5") (pin "4") (pinfunction "I_4") (pintype "input"))
    )
    (net (code "147") (name "TIN6") (class "Default")
      (node (ref "IC6") (pin "5") (pinfunction "+IN_5") (pintype "input"))
      (node (ref "U$1") (pin "PC0") (pinfunction "PC0_PC0") (pintype "bidirectional"))
      (node (ref "U$4") (pin "2") (pinfunction "I_2") (pintype "input"))
    )
    (net (code "148") (name "TIN7") (class "Default")
      (node (ref "IC6") (pin "10") (pinfunction "+IN_10") (pintype "input"))
      (node (ref "U$1") (pin "PC3") (pinfunction "PC3_PC3") (pintype "bidirectional"))
      (node (ref "U$4") (pin "4") (pinfunction "I_4") (pintype "input"))
    )
    (net (code "149") (name "TIN8") (class "Default")
      (node (ref "IC6") (pin "12") (pinfunction "+IN_12") (pintype "input"))
      (node (ref "U$1") (pin "PA0") (pinfunction "PA0_PA0") (pintype "bidirectional"))
      (node (ref "U$5") (pin "2") (pinfunction "I_2") (pintype "input"))
    )
    (net (code "150") (name "V+") (class "Default")
      (node (ref "AP1509") (pin "3") (pinfunction "FB_3") (pintype "bidirectional"))
      (node (ref "C1") (pin "1") (pinfunction "1_1") (pintype "passive"))
      (node (ref "C2") (pin "+") (pinfunction "+_+") (pintype "passive"))
      (node (ref "IC10") (pin "1") (pinfunction "FB_1") (pintype "input"))
      (node (ref "L1") (pin "1") (pinfunction "1_1") (pintype "passive"))
      (node (ref "U$1") (pin "E5V") (pinfunction "E5V_E5V") (pintype "power_in"))
    )
    (net (code "151") (name "unconnected-(H1-MOUNT-PadB3,3)") (class "Default")
      (node (ref "H1") (pin "B3,3") (pinfunction "MOUNT_B3,3") (pintype "passive"))
    )
    (net (code "152") (name "unconnected-(H2-MOUNT-PadB3,3)") (class "Default")
      (node (ref "H2") (pin "B3,3") (pinfunction "MOUNT_B3,3") (pintype "passive"))
    )
    (net (code "153") (name "unconnected-(H3-MOUNT-PadB3,3)") (class "Default")
      (node (ref "H3") (pin "B3,3") (pinfunction "MOUNT_B3,3") (pintype "passive"))
    )
    (net (code "154") (name "unconnected-(H4-MOUNT-PadB3,3)") (class "Default")
      (node (ref "H4") (pin "B3,3") (pinfunction "MOUNT_B3,3") (pintype "passive"))
    )
    (net (code "155") (name "unconnected-(J3-Pad2)") (class "Default")
      (node (ref "J3") (pin "2") (pinfunction "2_2") (pintype "passive"))
    )
    (net (code "156") (name "unconnected-(U$1-PadBOOT0)") (class "Default")
      (node (ref "U$1") (pin "BOOT0") (pinfunction "BOOT0_BOOT0") (pintype "bidirectional"))
    )
    (net (code "157") (name "unconnected-(U$1-PadIOREF2)") (class "Default")
      (node (ref "U$1") (pin "IOREF2") (pinfunction "IOREF2_IOREF2") (pintype "input"))
    )
    (net (code "158") (name "unconnected-(U$1-PadNC1-PF7)") (class "Default")
      (node (ref "U$1") (pin "NC1-PF7") (pinfunction "NC1-PF7_NC1-PF7") (pintype "bidirectional"))
    )
    (net (code "159") (name "unconnected-(U$1-PadNC2-PF6)") (class "Default")
      (node (ref "U$1") (pin "NC2-PF6") (pinfunction "NC2-PF6_NC2-PF6") (pintype "bidirectional"))
    )
    (net (code "160") (name "unconnected-(U$1-PadNC3)") (class "Default")
      (node (ref "U$1") (pin "NC3") (pinfunction "NC3_NC3") (pintype "no_connect"))
    )
    (net (code "161") (name "unconnected-(U$1-PadNC4)") (class "Default")
      (node (ref "U$1") (pin "NC4") (pinfunction "NC4_NC4") (pintype "no_connect"))
    )
    (net (code "162") (name "unconnected-(U$1-PadNC5-PD8)") (class "Default")
      (node (ref "U$1") (pin "NC5-PD8") (pinfunction "NC5-PD8_NC5-PD8") (pintype "bidirectional"))
    )
    (net (code "163") (name "unconnected-(U$1-PadNC6-PB11)") (class "Default")
      (node (ref "U$1") (pin "NC6-PB11") (pinfunction "NC6-PB11_NC6-PB11") (pintype "no_connect"))
    )
    (net (code "164") (name "unconnected-(U$1-PadNC7-PF5)") (class "Default")
      (node (ref "U$1") (pin "NC7-PF5") (pinfunction "NC7-PF5_NC7-PF5") (pintype "bidirectional"))
    )
    (net (code "165") (name "unconnected-(U$1-PadNC8-PF4)") (class "Default")
      (node (ref "U$1") (pin "NC8-PF4") (pinfunction "NC8-PF4_NC8-PF4") (pintype "bidirectional"))
    )
    (net (code "166") (name "unconnected-(U$1-PadNRESET)") (class "Default")
      (node (ref "U$1") (pin "NRESET") (pinfunction "NRESET_NRESET") (pintype "input"))
    )
    (net (code "167") (name "unconnected-(U$1-PadPA1)") (class "Default")
      (node (ref "U$1") (pin "PA1") (pinfunction "PA1_PA1") (pintype "bidirectional"))
    )
    (net (code "168") (name "unconnected-(U$1-PadPA2)") (class "Default")
      (node (ref "U$1") (pin "PA2") (pinfunction "PA2_PA2") (pintype "bidirectional"))
    )
    (net (code "169") (name "unconnected-(U$1-PadPA3)") (class "Default")
      (node (ref "U$1") (pin "PA3") (pinfunction "PA3_PA3") (pintype "bidirectional"))
    )
    (net (code "170") (name "unconnected-(U$1-PadPA5)") (class "Default")
      (node (ref "U$1") (pin "PA5") (pinfunction "PA5_PA5") (pintype "bidirectional"))
    )
    (net (code "171") (name "unconnected-(U$1-PadPA7)") (class "Default")
      (node (ref "U$1") (pin "PA7") (pinfunction "PA7_PA7") (pintype "bidirectional"))
    )
    (net (code "172") (name "unconnected-(U$1-PadPA9)") (class "Default")
      (node (ref "U$1") (pin "PA9") (pinfunction "PA9_PA9") (pintype "bidirectional"))
    )
    (net (code "173") (name "unconnected-(U$1-PadPA10)") (class "Default")
      (node (ref "U$1") (pin "PA10") (pinfunction "PA10_PA10") (pintype "bidirectional"))
    )
    (net (code "174") (name "unconnected-(U$1-PadPA11)") (class "Default")
      (node (ref "U$1") (pin "PA11") (pinfunction "PA11_PA11") (pintype "bidirectional"))
    )
    (net (code "175") (name "unconnected-(U$1-PadPA12)") (class "Default")
      (node (ref "U$1") (pin "PA12") (pinfunction "PA12_PA12") (pintype "bidirectional"))
    )
    (net (code "176") (name "unconnected-(U$1-PadPA13)") (class "Default")
      (node (ref "U$1") (pin "PA13") (pinfunction "PA13_PA13") (pintype "bidirectional"))
    )
    (net (code "177") (name "unconnected-(U$1-PadPA14)") (class "Default")
      (node (ref "U$1") (pin "PA14") (pinfunction "PA14_PA14") (pintype "bidirectional"))
    )
    (net (code "178") (name "unconnected-(U$1-PadPB0)") (class "Default")
      (node (ref "U$1") (pin "PB0") (pinfunction "PB0_PB0") (pintype "bidirectional"))
    )
    (net (code "179") (name "unconnected-(U$1-PadPB13)") (class "Default")
      (node (ref "U$1") (pin "PB13") (pinfunction "PB13_PB13") (pintype "bidirectional"))
    )
    (net (code "180") (name "unconnected-(U$1-PadPC1)") (class "Default")
      (node (ref "U$1") (pin "PC1") (pinfunction "PC1_PC1") (pintype "bidirectional"))
    )
    (net (code "181") (name "unconnected-(U$1-PadPC4)") (class "Default")
      (node (ref "U$1") (pin "PC4") (pinfunction "PC4_PC4") (pintype "bidirectional"))
    )
    (net (code "182") (name "unconnected-(U$1-PadPC5)") (class "Default")
      (node (ref "U$1") (pin "PC5") (pinfunction "PC5_PC5") (pintype "bidirectional"))
    )
    (net (code "183") (name "unconnected-(U$1-PadPC13)") (class "Default")
      (node (ref "U$1") (pin "PC13") (pinfunction "PC13_PC13") (pintype "bidirectional"))
    )
    (net (code "184") (name "unconnected-(U$1-PadPC14)") (class "Default")
      (node (ref "U$1") (pin "PC14") (pinfunction "PC14_PC14") (pintype "bidirectional"))
    )
    (net (code "185") (name "unconnected-(U$1-PadPC15)") (class "Default")
      (node (ref "U$1") (pin "PC15") (pinfunction "PC15_PC15") (pintype "bidirectional"))
    )
    (net (code "186") (name "unconnected-(U$1-PadPF0-PH0)") (class "Default")
      (node (ref "U$1") (pin "PF0-PH0") (pinfunction "PF0-PH0_PF0-PH0") (pintype "bidirectional"))
    )
  )
)
